# 2_0.net
KiCad netlist of a schematic drawn in Altium Designer
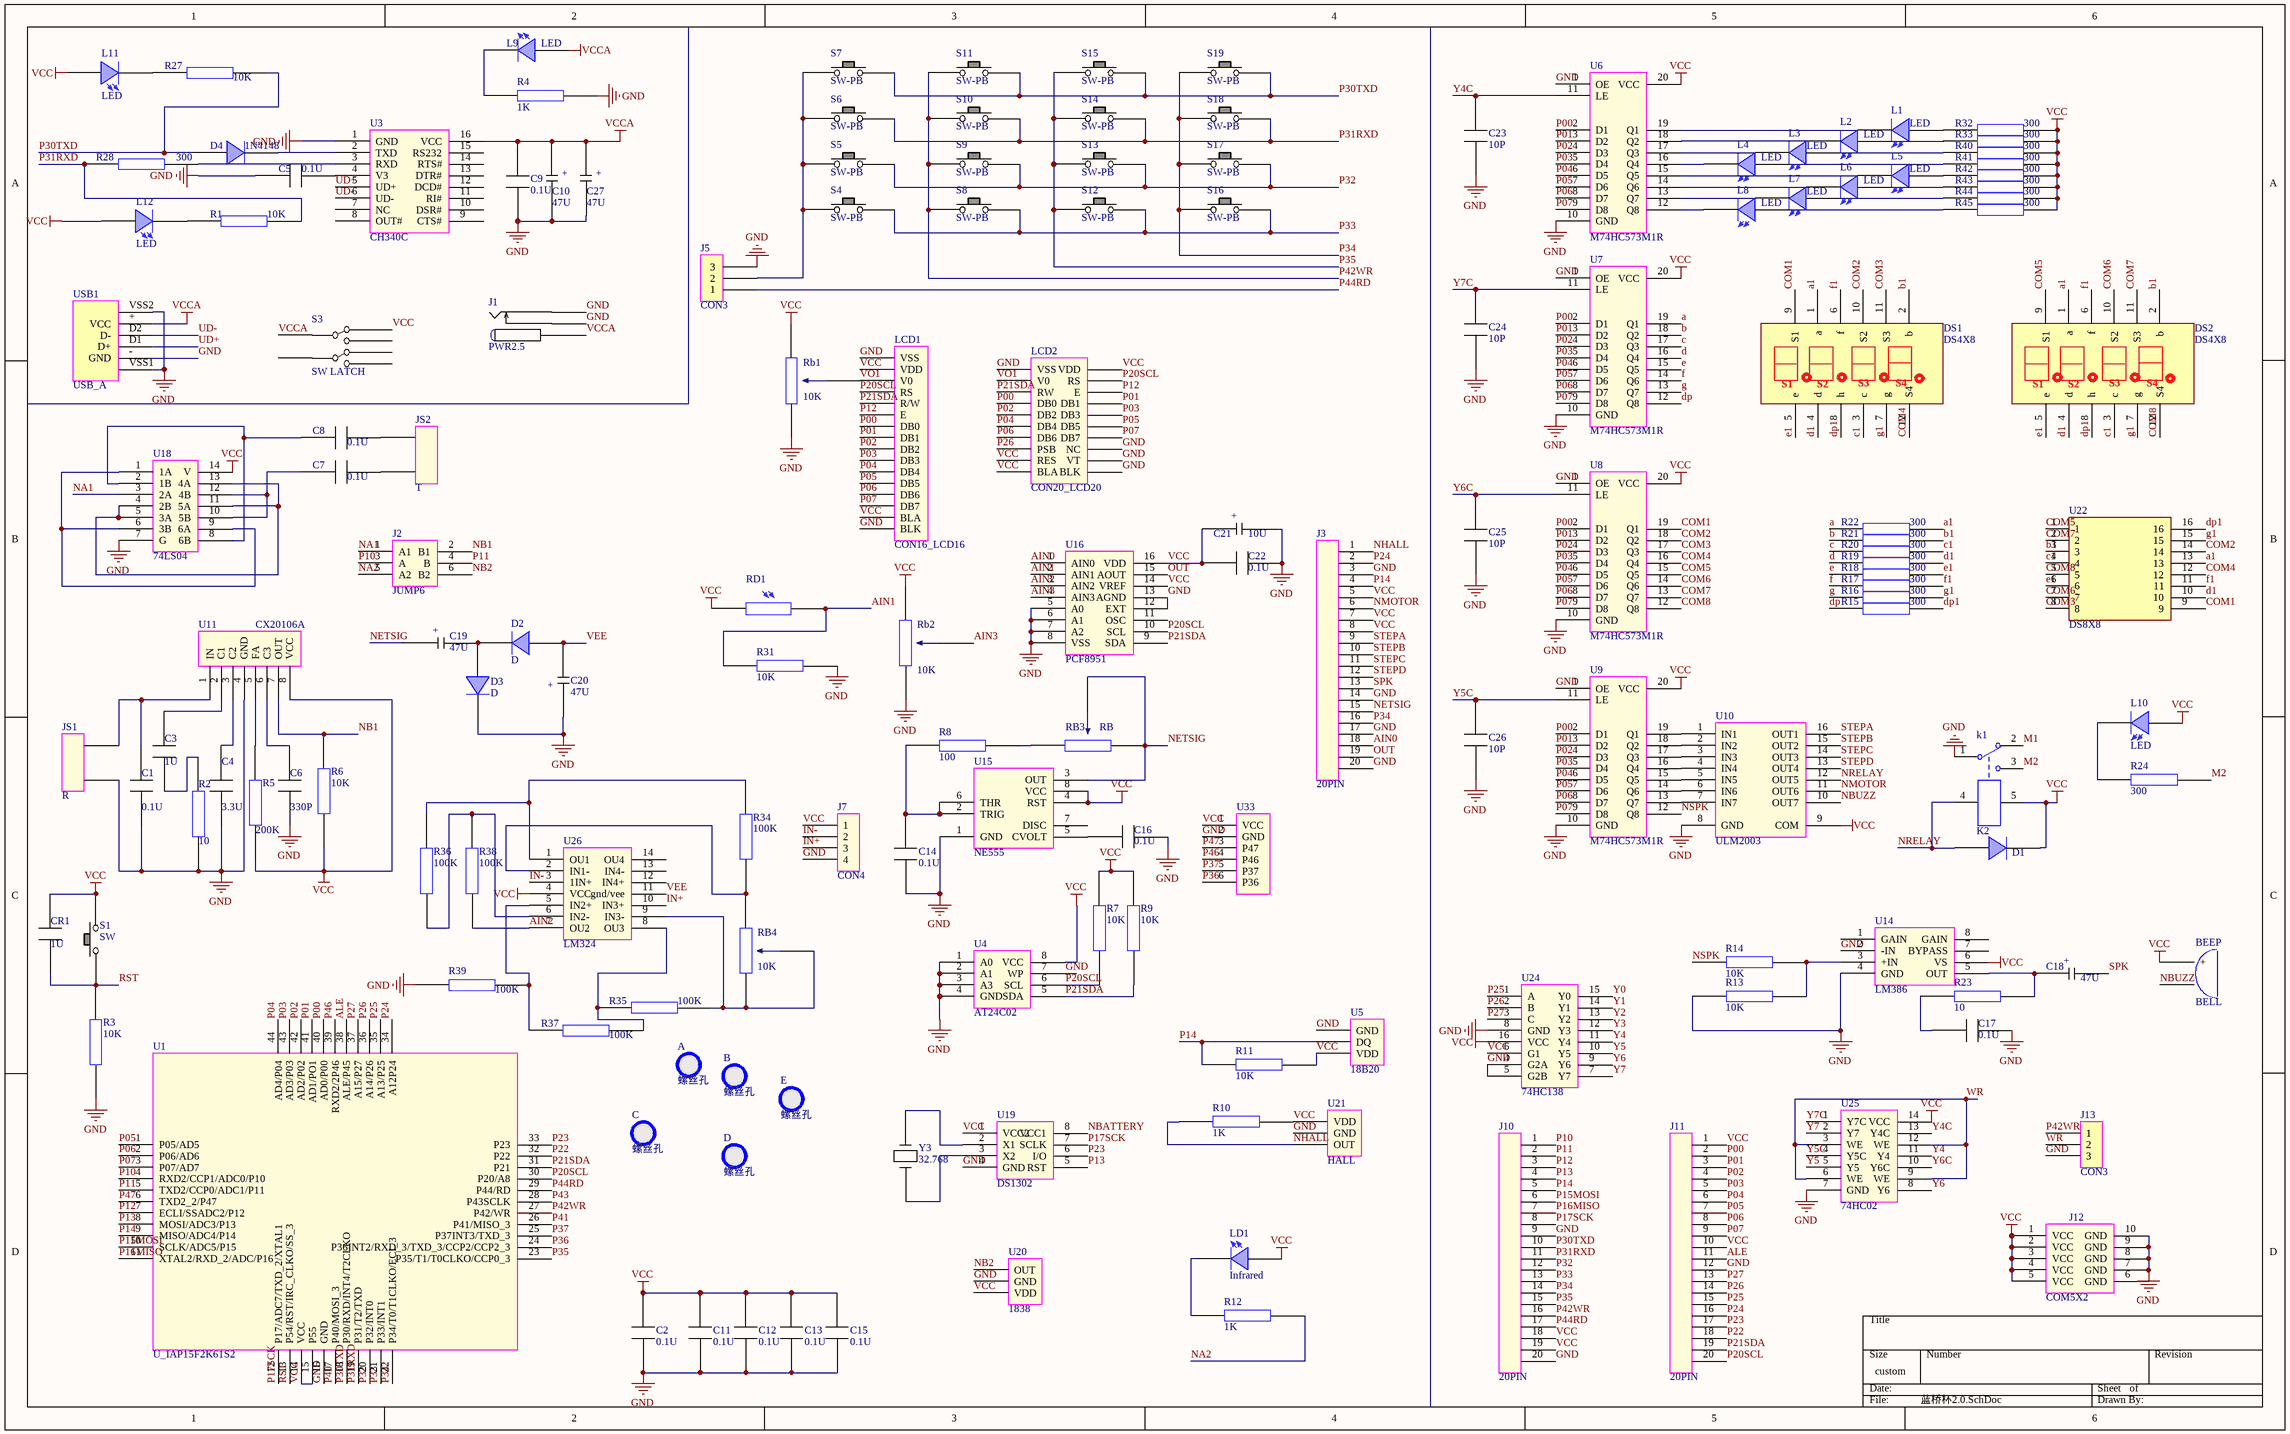
[diagram p0: 蓝桥杯2.0.SchDoc]

(export (version "E")
  (design (tool "Eeschema 10.0.6"))
  (components
    (comp (ref "A") (value "螺丝孔") (footprint "LUOSIKONG") (libsource (lib "蓝桥杯2.0板") (part "螺丝孔")))
    (comp (ref "B") (value "螺丝孔") (footprint "LUOSIKONG") (libsource (lib "蓝桥杯2.0板") (part "螺丝孔")))
    (comp (ref "BEEP") (value "BELL") (footprint "BUZZER") (libsource (lib "蓝桥杯2.0板") (part "BELL")))
    (comp (ref "C") (value "螺丝孔") (footprint "LUOSIKONG") (libsource (lib "蓝桥杯2.0板") (part "螺丝孔")))
    (comp (ref "C1") (value "0.1U") (footprint "C0805") (libsource (lib "蓝桥杯2.0板") (part "C")))
    (comp (ref "C2") (value "0.1U") (footprint "C0805") (libsource (lib "蓝桥杯2.0板") (part "C")))
    (comp (ref "C3") (value "1U") (footprint "C0805") (libsource (lib "蓝桥杯2.0板") (part "C")))
    (comp (ref "C4") (value "3.3U") (footprint "C0805") (libsource (lib "蓝桥杯2.0板") (part "C")))
    (comp (ref "C5") (value "0.1U") (footprint "C0805") (libsource (lib "蓝桥杯2.0板") (part "C")))
    (comp (ref "C6") (value "330P") (footprint "C0805") (libsource (lib "蓝桥杯2.0板") (part "C")))
    (comp (ref "C7") (value "0.1U") (footprint "C0805") (libsource (lib "蓝桥杯2.0板") (part "C")))
    (comp (ref "C8") (value "0.1U") (footprint "C0805") (libsource (lib "蓝桥杯2.0板") (part "C")))
    (comp (ref "C9") (value "0.1U") (footprint "C0805") (libsource (lib "蓝桥杯2.0板") (part "C")))
    (comp (ref "C10") (value "47U") (footprint "RVT 16V") (libsource (lib "蓝桥杯2.0板") (part "贴片电解电容")))
    (comp (ref "C11") (value "0.1U") (footprint "C0805") (libsource (lib "蓝桥杯2.0板") (part "C")))
    (comp (ref "C12") (value "0.1U") (footprint "C0805") (libsource (lib "蓝桥杯2.0板") (part "C")))
    (comp (ref "C13") (value "0.1U") (footprint "C0805") (libsource (lib "蓝桥杯2.0板") (part "C")))
    (comp (ref "C14") (value "0.1U") (footprint "C0805") (libsource (lib "蓝桥杯2.0板") (part "C")))
    (comp (ref "C15") (value "0.1U") (footprint "C0805") (libsource (lib "蓝桥杯2.0板") (part "C")))
    (comp (ref "C16") (value "0.1U") (footprint "C0805") (libsource (lib "蓝桥杯2.0板") (part "C")))
    (comp (ref "C17") (value "0.1U") (footprint "C0805") (libsource (lib "蓝桥杯2.0板") (part "C")))
    (comp (ref "C18") (value "47U") (footprint "RVT 16V") (libsource (lib "蓝桥杯2.0板") (part "贴片电解电容")))
    (comp (ref "C19") (value "47U") (footprint "RVT 16V") (libsource (lib "蓝桥杯2.0板") (part "贴片电解电容")))
    (comp (ref "C20") (value "47U") (footprint "RVT 16V") (libsource (lib "蓝桥杯2.0板") (part "贴片电解电容")))
    (comp (ref "C21") (value "10U") (footprint "RVT 16V") (libsource (lib "蓝桥杯2.0板") (part "贴片电解电容")))
    (comp (ref "C22") (value "0.1U") (footprint "C0805") (libsource (lib "蓝桥杯2.0板") (part "C")))
    (comp (ref "C23") (value "10P") (footprint "C0805") (libsource (lib "蓝桥杯2.0板") (part "C")))
    (comp (ref "C24") (value "10P") (footprint "C0805") (libsource (lib "蓝桥杯2.0板") (part "C")))
    (comp (ref "C25") (value "10P") (footprint "C0805") (libsource (lib "蓝桥杯2.0板") (part "C")))
    (comp (ref "C26") (value "10P") (footprint "C0805") (libsource (lib "蓝桥杯2.0板") (part "C")))
    (comp (ref "C27") (value "47U") (footprint "RVT 16V") (libsource (lib "蓝桥杯2.0板") (part "贴片电解电容")))
    (comp (ref "CR1") (value "1U") (footprint "C0805") (libsource (lib "蓝桥杯2.0板") (part "C")))
    (comp (ref "D") (value "螺丝孔") (footprint "LUOSIKONG") (libsource (lib "蓝桥杯2.0板") (part "螺丝孔")))
    (comp (ref "D1") (value "D") (footprint "D-DIODE-0805") (libsource (lib "蓝桥杯2.0板") (part "D")))
    (comp (ref "D2") (value "D") (footprint "D-DIODE-0805") (libsource (lib "蓝桥杯2.0板") (part "D")))
    (comp (ref "D3") (value "D") (footprint "D-DIODE-0805") (libsource (lib "蓝桥杯2.0板") (part "D")))
    (comp (ref "D4") (value "1N4148") (footprint "D-DIODE-0805") (libsource (lib "蓝桥杯2.0板") (part "D")))
    (comp (ref "DS1") (value "DS4X8") (footprint "DPY-4X8") (libsource (lib "蓝桥杯2.0板") (part "DS4X8")))
    (comp (ref "DS2") (value "DS4X8") (footprint "DPY-4X8") (libsource (lib "蓝桥杯2.0板") (part "DS4X8")))
    (comp (ref "E") (value "螺丝孔") (footprint "LUOSIKONG") (libsource (lib "蓝桥杯2.0板") (part "螺丝孔")))
    (comp (ref "J1") (value "PWR2.5") (footprint "PW 2.5") (libsource (lib "蓝桥杯2.0板") (part "PWR2.5")))
    (comp (ref "J2") (value "JUMP6") (footprint "SIP-3X2") (libsource (lib "蓝桥杯2.0板") (part "OP6")))
    (comp (ref "J3")
      (value "20PIN")
      (footprint "SIP-20 - duplicate")
      (libsource (lib "蓝桥杯2.0板") (part "P20"))
    )
    (comp (ref "J5") (value "CON3") (footprint "SIP-3") (libsource (lib "") (part "COM3_1")))
    (comp (ref "J7") (value "CON4") (footprint "SIP-4") (libsource (lib "蓝桥杯2.0板") (part "COM4")))
    (comp (ref "J10")
      (value "20PIN")
      (footprint "SIP-20 - duplicate")
      (libsource (lib "蓝桥杯2.0板") (part "P20"))
    )
    (comp (ref "J11")
      (value "20PIN")
      (footprint "SIP-20 - duplicate")
      (libsource (lib "蓝桥杯2.0板") (part "P20"))
    )
    (comp (ref "J12") (value "COM5X2") (footprint "SIP-5X2") (libsource (lib "蓝桥杯2.0板") (part "COM5X2")))
    (comp (ref "J13") (value "CON3") (footprint "SIP-3") (libsource (lib "蓝桥杯2.0板") (part "COM3")))
    (comp (ref "JS1") (value "R") (footprint "RT-16") (libsource (lib "蓝桥杯2.0板") (part "JS")))
    (comp (ref "JS2") (value "T") (footprint "RT-16") (libsource (lib "") (part "JS_1")))
    (comp (ref "k1") (value "K2") (footprint "HK-4100-F") (libsource (lib "蓝桥杯2.0板") (part "K2")))
    (comp (ref "L1") (value "LED") (footprint "L0805") (libsource (lib "蓝桥杯2.0板") (part "LED")))
    (comp (ref "L2") (value "LED") (footprint "L0805") (libsource (lib "蓝桥杯2.0板") (part "LED")))
    (comp (ref "L3") (value "LED") (footprint "L0805") (libsource (lib "蓝桥杯2.0板") (part "LED")))
    (comp (ref "L4") (value "LED") (footprint "L0805") (libsource (lib "蓝桥杯2.0板") (part "LED")))
    (comp (ref "L5") (value "LED") (footprint "L0805") (libsource (lib "蓝桥杯2.0板") (part "LED")))
    (comp (ref "L6") (value "LED") (footprint "L0805") (libsource (lib "蓝桥杯2.0板") (part "LED")))
    (comp (ref "L7") (value "LED") (footprint "L0805") (libsource (lib "蓝桥杯2.0板") (part "LED")))
    (comp (ref "L8") (value "LED") (footprint "L0805") (libsource (lib "蓝桥杯2.0板") (part "LED")))
    (comp (ref "L9") (value "LED") (footprint "L0805") (libsource (lib "蓝桥杯2.0板") (part "LED")))
    (comp (ref "L10") (value "LED") (footprint "L0805") (libsource (lib "蓝桥杯2.0板") (part "LED")))
    (comp (ref "L11") (value "LED") (footprint "L0805") (libsource (lib "蓝桥杯2.0板") (part "LED")))
    (comp (ref "L12") (value "LED") (footprint "L0805") (libsource (lib "蓝桥杯2.0板") (part "LED")))
    (comp (ref "LCD1") (value "CON16_LCD16") (footprint "SIP-16") (libsource (lib "蓝桥杯2.0板") (part "LCD16")))
    (comp (ref "LCD2") (value "CON20_LCD20") (footprint "SIP-20") (libsource (lib "蓝桥杯2.0板") (part "LCD20")))
    (comp (ref "LD1") (value "Infrared") (footprint "LED-LNF") (libsource (lib "蓝桥杯2.0板") (part "INF")))
    (comp (ref "R1") (value "10K") (footprint "R0805") (libsource (lib "蓝桥杯2.0板") (part "R")))
    (comp (ref "R2") (value "10") (footprint "R0805") (libsource (lib "蓝桥杯2.0板") (part "R")))
    (comp (ref "R3") (value "10K") (footprint "R0805") (libsource (lib "蓝桥杯2.0板") (part "R")))
    (comp (ref "R4") (value "1K") (footprint "R0805") (libsource (lib "蓝桥杯2.0板") (part "R")))
    (comp (ref "R5") (value "200K") (footprint "R0805") (libsource (lib "蓝桥杯2.0板") (part "R")))
    (comp (ref "R6") (value "10K") (footprint "R0805") (libsource (lib "蓝桥杯2.0板") (part "R")))
    (comp (ref "R7") (value "10K") (footprint "R0805") (libsource (lib "蓝桥杯2.0板") (part "R")))
    (comp (ref "R8") (value "100") (footprint "R0805") (libsource (lib "蓝桥杯2.0板") (part "R")))
    (comp (ref "R9") (value "10K") (footprint "R0805") (libsource (lib "蓝桥杯2.0板") (part "R")))
    (comp (ref "R10") (value "1K") (footprint "R0805") (libsource (lib "蓝桥杯2.0板") (part "R")))
    (comp (ref "R11") (value "10K") (footprint "R0805") (libsource (lib "蓝桥杯2.0板") (part "R")))
    (comp (ref "R12") (value "1K") (footprint "R0805") (libsource (lib "蓝桥杯2.0板") (part "R")))
    (comp (ref "R13") (value "10K") (footprint "R0805") (libsource (lib "蓝桥杯2.0板") (part "R")))
    (comp (ref "R14") (value "10K") (footprint "R0805") (libsource (lib "蓝桥杯2.0板") (part "R")))
    (comp (ref "R15") (value "300") (footprint "R0805") (libsource (lib "蓝桥杯2.0板") (part "R")))
    (comp (ref "R16") (value "300") (footprint "R0805") (libsource (lib "蓝桥杯2.0板") (part "R")))
    (comp (ref "R17") (value "300") (footprint "R0805") (libsource (lib "蓝桥杯2.0板") (part "R")))
    (comp (ref "R18") (value "300") (footprint "R0805") (libsource (lib "蓝桥杯2.0板") (part "R")))
    (comp (ref "R19") (value "300") (footprint "R0805") (libsource (lib "蓝桥杯2.0板") (part "R")))
    (comp (ref "R20") (value "300") (footprint "R0805") (libsource (lib "蓝桥杯2.0板") (part "R")))
    (comp (ref "R21") (value "300") (footprint "R0805") (libsource (lib "蓝桥杯2.0板") (part "R")))
    (comp (ref "R22") (value "300") (footprint "R0805") (libsource (lib "蓝桥杯2.0板") (part "R")))
    (comp (ref "R23") (value "10") (footprint "R0805") (libsource (lib "蓝桥杯2.0板") (part "R")))
    (comp (ref "R24") (value "300") (footprint "R0805") (libsource (lib "蓝桥杯2.0板") (part "R")))
    (comp (ref "R27") (value "10K") (footprint "R0805") (libsource (lib "蓝桥杯2.0板") (part "R")))
    (comp (ref "R28") (value "300") (footprint "R0805") (libsource (lib "蓝桥杯2.0板") (part "R")))
    (comp (ref "R31") (value "10K") (footprint "R0805") (libsource (lib "蓝桥杯2.0板") (part "R")))
    (comp (ref "R32") (value "300") (footprint "R0805") (libsource (lib "蓝桥杯2.0板") (part "R")))
    (comp (ref "R33") (value "300") (footprint "R0805") (libsource (lib "蓝桥杯2.0板") (part "R")))
    (comp (ref "R34") (value "100K") (footprint "R0805") (libsource (lib "蓝桥杯2.0板") (part "R")))
    (comp (ref "R35") (value "100K") (footprint "R0805") (libsource (lib "蓝桥杯2.0板") (part "R")))
    (comp (ref "R36") (value "100K") (footprint "R0805") (libsource (lib "蓝桥杯2.0板") (part "R")))
    (comp (ref "R37") (value "100K") (footprint "R0805") (libsource (lib "蓝桥杯2.0板") (part "R")))
    (comp (ref "R38") (value "100K") (footprint "R0805") (libsource (lib "蓝桥杯2.0板") (part "R")))
    (comp (ref "R39") (value "100K") (footprint "R0805") (libsource (lib "蓝桥杯2.0板") (part "R")))
    (comp (ref "R40") (value "300") (footprint "R0805") (libsource (lib "蓝桥杯2.0板") (part "R")))
    (comp (ref "R41") (value "300") (footprint "R0805") (libsource (lib "蓝桥杯2.0板") (part "R")))
    (comp (ref "R42") (value "300") (footprint "R0805") (libsource (lib "蓝桥杯2.0板") (part "R")))
    (comp (ref "R43") (value "300") (footprint "R0805") (libsource (lib "蓝桥杯2.0板") (part "R")))
    (comp (ref "R44") (value "300") (footprint "R0805") (libsource (lib "蓝桥杯2.0板") (part "R")))
    (comp (ref "R45") (value "300") (footprint "R0805") (libsource (lib "蓝桥杯2.0板") (part "R")))
    (comp (ref "Rb1") (value "10K") (footprint "VR-3 10") (libsource (lib "蓝桥杯2.0板") (part "RB")))
    (comp (ref "Rb2") (value "10K") (footprint "VR-3 10") (libsource (lib "蓝桥杯2.0板") (part "RB")))
    (comp (ref "RB3") (value "RB") (footprint "VR-3 10") (libsource (lib "蓝桥杯2.0板") (part "RB")))
    (comp (ref "RB4") (value "10K") (footprint "VR-3 10") (libsource (lib "蓝桥杯2.0板") (part "RB")))
    (comp (ref "RD1") (value "RD") (footprint "AXIAL-0.2") (libsource (lib "蓝桥杯2.0板") (part "RD")))
    (comp (ref "S1") (value "SW") (footprint "SKOE") (libsource (lib "") (part "贴片按键_1")))
    (comp (ref "S3") (value "SW LATCH") (footprint "SW-PB") (libsource (lib "蓝桥杯2.0板") (part "KG")))
    (comp (ref "S4") (value "SW-PB") (footprint "SKOE") (libsource (lib "蓝桥杯2.0板") (part "贴片按键")))
    (comp (ref "S5") (value "SW-PB") (footprint "SKOE") (libsource (lib "蓝桥杯2.0板") (part "贴片按键")))
    (comp (ref "S6") (value "SW-PB") (footprint "SKOE") (libsource (lib "蓝桥杯2.0板") (part "贴片按键")))
    (comp (ref "S7") (value "SW-PB") (footprint "SKOE") (libsource (lib "蓝桥杯2.0板") (part "贴片按键")))
    (comp (ref "S8") (value "SW-PB") (footprint "SKOE") (libsource (lib "蓝桥杯2.0板") (part "贴片按键")))
    (comp (ref "S9") (value "SW-PB") (footprint "SKOE") (libsource (lib "蓝桥杯2.0板") (part "贴片按键")))
    (comp (ref "S10") (value "SW-PB") (footprint "SKOE") (libsource (lib "蓝桥杯2.0板") (part "贴片按键")))
    (comp (ref "S11") (value "SW-PB") (footprint "SKOE") (libsource (lib "蓝桥杯2.0板") (part "贴片按键")))
    (comp (ref "S12") (value "SW-PB") (footprint "SKOE") (libsource (lib "蓝桥杯2.0板") (part "贴片按键")))
    (comp (ref "S13") (value "SW-PB") (footprint "SKOE") (libsource (lib "蓝桥杯2.0板") (part "贴片按键")))
    (comp (ref "S14") (value "SW-PB") (footprint "SKOE") (libsource (lib "蓝桥杯2.0板") (part "贴片按键")))
    (comp (ref "S15") (value "SW-PB") (footprint "SKOE") (libsource (lib "蓝桥杯2.0板") (part "贴片按键")))
    (comp (ref "S16") (value "SW-PB") (footprint "SKOE") (libsource (lib "蓝桥杯2.0板") (part "贴片按键")))
    (comp (ref "S17") (value "SW-PB") (footprint "SKOE") (libsource (lib "蓝桥杯2.0板") (part "贴片按键")))
    (comp (ref "S18") (value "SW-PB") (footprint "SKOE") (libsource (lib "蓝桥杯2.0板") (part "贴片按键")))
    (comp (ref "S19") (value "SW-PB") (footprint "SKOE") (libsource (lib "蓝桥杯2.0板") (part "贴片按键")))
    (comp (ref "U1")
      (value "U_IAP15F2K61S2")
      (footprint "LQFP44 - duplicate")
      (libsource (lib "转接板元件库") (part "STC15"))
    )
    (comp (ref "U3") (value "CH340C") (footprint "SOP-16") (libsource (lib "蓝桥杯2.0板") (part "CH340C")))
    (comp (ref "U4") (value "AT24C02") (footprint "SOP-8") (libsource (lib "蓝桥杯2.0板") (part "AT24C02")))
    (comp (ref "U5") (value "18B20") (footprint "TO-92") (libsource (lib "蓝桥杯2.0板") (part "18B20")))
    (comp (ref "U6")
      (value "M74HC573M1R")
      (footprint "TSOP-20(宽体)")
      (libsource (lib "蓝桥杯2.0板") (part "CH573"))
    )
    (comp (ref "U7")
      (value "M74HC573M1R")
      (footprint "TSOP-20(宽体)")
      (libsource (lib "蓝桥杯2.0板") (part "CH573"))
    )
    (comp (ref "U8")
      (value "M74HC573M1R")
      (footprint "TSOP-20(宽体)")
      (libsource (lib "蓝桥杯2.0板") (part "CH573"))
    )
    (comp (ref "U9")
      (value "M74HC573M1R")
      (footprint "TSOP-20(宽体)")
      (libsource (lib "蓝桥杯2.0板") (part "CH573"))
    )
    (comp (ref "U10") (value "ULM2003") (footprint "SOP-16") (libsource (lib "蓝桥杯2.0板") (part "ULM2003")))
    (comp (ref "U11") (value "CX20106A") (footprint "DIP-8") (libsource (lib "蓝桥杯2.0板") (part "CX20106A")))
    (comp (ref "U14") (value "LM386") (footprint "SOP-8") (libsource (lib "蓝桥杯2.0板") (part "LM386")))
    (comp (ref "U15") (value "NE555") (footprint "SOP-8") (libsource (lib "蓝桥杯2.0板") (part "NE555")))
    (comp (ref "U16")
      (value "PCF8951")
      (footprint "TSOP-16(宽体)")
      (libsource (lib "蓝桥杯2.0板") (part "PCF8951"))
    )
    (comp (ref "U18") (value "74LS04") (footprint "SOP-14") (libsource (lib "蓝桥杯2.0板") (part "74LS04")))
    (comp (ref "U19") (value "DS1302") (footprint "SOP-8") (libsource (lib "蓝桥杯2.0板") (part "DS1302")))
    (comp (ref "U20") (value "1838") (footprint "TO-92-A") (libsource (lib "蓝桥杯2.0板") (part "1838")))
    (comp (ref "U21") (value "HALL") (footprint "TO92-3") (libsource (lib "蓝桥杯2.0板") (part "HALL")))
    (comp (ref "U22") (value "DS8X8") (footprint "DPY-8X8") (libsource (lib "蓝桥杯2.0板") (part "DS8X8")))
    (comp (ref "U24") (value "74HC138") (footprint "SOP-16") (libsource (lib "蓝桥杯2.0板") (part "74HC138")))
    (comp (ref "U25") (value "74HC02") (footprint "SOP-14") (libsource (lib "蓝桥杯2.0板") (part "74HC02")))
    (comp (ref "U26") (value "LM324") (footprint "SOP-14") (libsource (lib "蓝桥杯2.0板") (part "LM324")))
    (comp (ref "U33") (value "~") (footprint "D0") (libsource (lib "蓝桥杯2.0板") (part "洞洞板")))
    (comp (ref "USB1") (value "USB_A") (footprint "USB-B") (libsource (lib "蓝桥杯2.0板") (part "USB_A")))
    (comp (ref "Y3") (value "32.768") (footprint "XTAL1-37K") (libsource (lib "蓝桥杯2.0板") (part "Y3")))
  )
  (nets
    (net (code "1") (name "/AIN0") (class "Default")
      (node (ref "J3") (pin "18") (pinfunction "18_18") (pintype "passive"))
      (node (ref "U16") (pin "1") (pinfunction "AIN0_1") (pintype "passive"))
    )
    (net (code "2") (name "/AIN1") (class "Default")
      (node (ref "R31") (pin "2") (pinfunction "2_2") (pintype "passive"))
      (node (ref "RD1") (pin "2") (pinfunction "2_2") (pintype "passive"))
      (node (ref "U16") (pin "2") (pinfunction "AIN1_2") (pintype "passive"))
    )
    (net (code "3") (name "/AIN2") (class "Default")
      (node (ref "R38") (pin "2") (pinfunction "2_2") (pintype "passive"))
      (node (ref "U16") (pin "3") (pinfunction "AIN2_3") (pintype "passive"))
      (node (ref "U26") (pin "7") (pinfunction "OU2_7") (pintype "passive"))
    )
    (net (code "4") (name "/AIN3") (class "Default")
      (node (ref "Rb2") (pin "2") (pinfunction "2_2") (pintype "passive"))
      (node (ref "U16") (pin "4") (pinfunction "AIN3_4") (pintype "passive"))
    )
    (net (code "5") (name "/ALE") (class "Default")
      (node (ref "J11") (pin "11") (pinfunction "11_11") (pintype "passive"))
      (node (ref "U1") (pin "38") (pinfunction "ALE/P45_38") (pintype "passive"))
    )
    (net (code "6") (name "/COM1") (class "Default")
      (node (ref "DS1") (pin "9") (pinfunction "S1_9") (pintype "passive"))
      (node (ref "U22") (pin "9") (pinfunction "9_9") (pintype "passive"))
      (node (ref "U8") (pin "19") (pinfunction "Q1_19") (pintype "passive"))
    )
    (net (code "7") (name "/COM2") (class "Default")
      (node (ref "DS1") (pin "10") (pinfunction "S2_10") (pintype "passive"))
      (node (ref "U22") (pin "14") (pinfunction "14_14") (pintype "passive"))
      (node (ref "U8") (pin "18") (pinfunction "Q2_18") (pintype "passive"))
    )
    (net (code "8") (name "/COM3") (class "Default")
      (node (ref "DS1") (pin "11") (pinfunction "S3_11") (pintype "passive"))
      (node (ref "U22") (pin "8") (pinfunction "8_8") (pintype "passive"))
      (node (ref "U8") (pin "17") (pinfunction "Q3_17") (pintype "passive"))
    )
    (net (code "9") (name "/COM4") (class "Default")
      (node (ref "DS1") (pin "12") (pinfunction "S4_12") (pintype "passive"))
      (node (ref "U22") (pin "12") (pinfunction "12_12") (pintype "passive"))
      (node (ref "U8") (pin "16") (pinfunction "Q4_16") (pintype "passive"))
    )
    (net (code "10") (name "/COM5") (class "Default")
      (node (ref "DS2") (pin "9") (pinfunction "S1_9") (pintype "passive"))
      (node (ref "U22") (pin "1") (pinfunction "1_1") (pintype "passive"))
      (node (ref "U8") (pin "15") (pinfunction "Q5_15") (pintype "passive"))
    )
    (net (code "11") (name "/COM6") (class "Default")
      (node (ref "DS2") (pin "10") (pinfunction "S2_10") (pintype "passive"))
      (node (ref "U22") (pin "7") (pinfunction "7_7") (pintype "passive"))
      (node (ref "U8") (pin "14") (pinfunction "Q6_14") (pintype "passive"))
    )
    (net (code "12") (name "/COM7") (class "Default")
      (node (ref "DS2") (pin "11") (pinfunction "S3_11") (pintype "passive"))
      (node (ref "U22") (pin "2") (pinfunction "2_2") (pintype "passive"))
      (node (ref "U8") (pin "13") (pinfunction "Q7_13") (pintype "passive"))
    )
    (net (code "13") (name "/COM8") (class "Default")
      (node (ref "DS2") (pin "12") (pinfunction "S4_12") (pintype "passive"))
      (node (ref "U22") (pin "5") (pinfunction "5_5") (pintype "passive"))
      (node (ref "U8") (pin "12") (pinfunction "Q8_12") (pintype "passive"))
    )
    (net (code "14") (name "/IN+") (class "Default")
      (node (ref "J7") (pin "3") (pinfunction "3_3") (pintype "passive"))
      (node (ref "U26") (pin "10") (pinfunction "IN3+_10") (pintype "passive"))
    )
    (net (code "15") (name "/IN-") (class "Default")
      (node (ref "J7") (pin "2") (pinfunction "2_2") (pintype "passive"))
      (node (ref "U26") (pin "3") (pinfunction "1IN+_3") (pintype "passive"))
    )
    (net (code "16") (name "/M1") (class "Default")
      (node (ref "k1") (pin "2") (pinfunction "2_2") (pintype "passive"))
    )
    (net (code "17") (name "/M2") (class "Default")
      (node (ref "R24") (pin "1") (pinfunction "1_1") (pintype "passive"))
      (node (ref "k1") (pin "3") (pinfunction "3_3") (pintype "passive"))
    )
    (net (code "18") (name "/NA1") (class "Default")
      (node (ref "J2") (pin "1") (pinfunction "A1_1") (pintype "passive"))
      (node (ref "U18") (pin "3") (pinfunction "2A_3") (pintype "passive"))
    )
    (net (code "19") (name "/NA2") (class "Default")
      (node (ref "J2") (pin "5") (pinfunction "A2_5") (pintype "passive"))
      (node (ref "R12") (pin "1") (pinfunction "1_1") (pintype "passive"))
    )
    (net (code "20") (name "/NB1") (class "Default")
      (node (ref "J2") (pin "2") (pinfunction "B1_2") (pintype "passive"))
      (node (ref "R6") (pin "2") (pinfunction "2_2") (pintype "passive"))
      (node (ref "U11") (pin "7") (pinfunction "OUT_7") (pintype "passive"))
    )
    (net (code "21") (name "/NB2") (class "Default")
      (node (ref "J2") (pin "6") (pinfunction "B2_6") (pintype "passive"))
      (node (ref "U20") (pin "1") (pinfunction "OUT_1") (pintype "passive"))
    )
    (net (code "22") (name "/NBATTERY") (class "Default")
      (node (ref "U19") (pin "8") (pinfunction "VCC1_8") (pintype "passive"))
    )
    (net (code "23") (name "/NBUZZ") (class "Default")
      (node (ref "BEEP") (pin "2") (pinfunction "2_2") (pintype "passive"))
      (node (ref "U10") (pin "10") (pinfunction "OUT7_10") (pintype "passive"))
    )
    (net (code "24") (name "/NETSIG") (class "Default")
      (node (ref "C19") (pin "1") (pinfunction "+_1") (pintype "passive"))
      (node (ref "J3") (pin "15") (pinfunction "15_15") (pintype "passive"))
      (node (ref "RB3") (pin "2") (pinfunction "2_2") (pintype "passive"))
      (node (ref "RB3") (pin "3") (pinfunction "3_3") (pintype "passive"))
      (node (ref "U15") (pin "3") (pinfunction "OUT_3") (pintype "passive"))
    )
    (net (code "25") (name "/NHALL") (class "Default")
      (node (ref "J3") (pin "1") (pinfunction "1_1") (pintype "passive"))
      (node (ref "R10") (pin "2") (pinfunction "2_2") (pintype "passive"))
      (node (ref "U21") (pin "3") (pinfunction "OUT_3") (pintype "passive"))
    )
    (net (code "26") (name "/NMOTOR") (class "Default")
      (node (ref "J3") (pin "6") (pinfunction "6_6") (pintype "passive"))
      (node (ref "U10") (pin "11") (pinfunction "OUT6_11") (pintype "passive"))
    )
    (net (code "27") (name "/NRELAY") (class "Default")
      (node (ref "D1") (pin "1") (pinfunction "1_1") (pintype "passive"))
      (node (ref "U10") (pin "12") (pinfunction "OUT5_12") (pintype "passive"))
      (node (ref "k1") (pin "4") (pinfunction "4_4") (pintype "passive"))
    )
    (net (code "28") (name "/NSPK") (class "Default")
      (node (ref "R14") (pin "2") (pinfunction "2_2") (pintype "passive"))
      (node (ref "U9") (pin "12") (pinfunction "Q8_12") (pintype "passive"))
    )
    (net (code "29") (name "/OUT") (class "Default")
      (node (ref "J3") (pin "19") (pinfunction "19_19") (pintype "passive"))
      (node (ref "U16") (pin "15") (pinfunction "AOUT_15") (pintype "passive"))
    )
    (net (code "30") (name "/P00") (class "Default")
      (node (ref "J11") (pin "2") (pinfunction "2_2") (pintype "passive"))
      (node (ref "LCD1") (pin "7") (pinfunction "DB0_7") (pintype "passive"))
      (node (ref "LCD2") (pin "7") (pinfunction "DB0_7") (pintype "passive"))
      (node (ref "U1") (pin "40") (pinfunction "AD0/P00_40") (pintype "passive"))
      (node (ref "U6") (pin "2") (pinfunction "D1_2") (pintype "passive"))
      (node (ref "U7") (pin "2") (pinfunction "D1_2") (pintype "passive"))
      (node (ref "U8") (pin "2") (pinfunction "D1_2") (pintype "passive"))
      (node (ref "U9") (pin "2") (pinfunction "D1_2") (pintype "passive"))
    )
    (net (code "31") (name "/P01") (class "Default")
      (node (ref "J11") (pin "3") (pinfunction "3_3") (pintype "passive"))
      (node (ref "LCD1") (pin "8") (pinfunction "DB1_8") (pintype "passive"))
      (node (ref "LCD2") (pin "8") (pinfunction "DB1_8") (pintype "passive"))
      (node (ref "U1") (pin "41") (pinfunction "AD1/PO1_41") (pintype "passive"))
      (node (ref "U6") (pin "3") (pinfunction "D2_3") (pintype "passive"))
      (node (ref "U7") (pin "3") (pinfunction "D2_3") (pintype "passive"))
      (node (ref "U8") (pin "3") (pinfunction "D2_3") (pintype "passive"))
      (node (ref "U9") (pin "3") (pinfunction "D2_3") (pintype "passive"))
    )
    (net (code "32") (name "/P02") (class "Default")
      (node (ref "J11") (pin "4") (pinfunction "4_4") (pintype "passive"))
      (node (ref "LCD1") (pin "9") (pinfunction "DB2_9") (pintype "passive"))
      (node (ref "LCD2") (pin "9") (pinfunction "DB2_9") (pintype "passive"))
      (node (ref "U1") (pin "42") (pinfunction "AD2/P02_42") (pintype "passive"))
      (node (ref "U6") (pin "4") (pinfunction "D3_4") (pintype "passive"))
      (node (ref "U7") (pin "4") (pinfunction "D3_4") (pintype "passive"))
      (node (ref "U8") (pin "4") (pinfunction "D3_4") (pintype "passive"))
      (node (ref "U9") (pin "4") (pinfunction "D3_4") (pintype "passive"))
    )
    (net (code "33") (name "/P03") (class "Default")
      (node (ref "J11") (pin "5") (pinfunction "5_5") (pintype "passive"))
      (node (ref "LCD1") (pin "10") (pinfunction "DB3_10") (pintype "passive"))
      (node (ref "LCD2") (pin "10") (pinfunction "DB3_10") (pintype "passive"))
      (node (ref "U1") (pin "43") (pinfunction "AD3/P03_43") (pintype "passive"))
      (node (ref "U6") (pin "5") (pinfunction "D4_5") (pintype "passive"))
      (node (ref "U7") (pin "5") (pinfunction "D4_5") (pintype "passive"))
      (node (ref "U8") (pin "5") (pinfunction "D4_5") (pintype "passive"))
      (node (ref "U9") (pin "5") (pinfunction "D4_5") (pintype "passive"))
    )
    (net (code "34") (name "/P04") (class "Default")
      (node (ref "J11") (pin "6") (pinfunction "6_6") (pintype "passive"))
      (node (ref "LCD1") (pin "11") (pinfunction "DB4_11") (pintype "passive"))
      (node (ref "LCD2") (pin "11") (pinfunction "DB4_11") (pintype "passive"))
      (node (ref "U1") (pin "44") (pinfunction "AD4/P04_44") (pintype "passive"))
      (node (ref "U6") (pin "6") (pinfunction "D5_6") (pintype "passive"))
      (node (ref "U7") (pin "6") (pinfunction "D5_6") (pintype "passive"))
      (node (ref "U8") (pin "6") (pinfunction "D5_6") (pintype "passive"))
      (node (ref "U9") (pin "6") (pinfunction "D5_6") (pintype "passive"))
    )
    (net (code "35") (name "/P05") (class "Default")
      (node (ref "J11") (pin "7") (pinfunction "7_7") (pintype "passive"))
      (node (ref "LCD1") (pin "12") (pinfunction "DB5_12") (pintype "passive"))
      (node (ref "LCD2") (pin "12") (pinfunction "DB5_12") (pintype "passive"))
      (node (ref "U1") (pin "1") (pinfunction "P05/AD5_1") (pintype "passive"))
      (node (ref "U6") (pin "7") (pinfunction "D6_7") (pintype "passive"))
      (node (ref "U7") (pin "7") (pinfunction "D6_7") (pintype "passive"))
      (node (ref "U8") (pin "7") (pinfunction "D6_7") (pintype "passive"))
      (node (ref "U9") (pin "7") (pinfunction "D6_7") (pintype "passive"))
    )
    (net (code "36") (name "/P06") (class "Default")
      (node (ref "J11") (pin "8") (pinfunction "8_8") (pintype "passive"))
      (node (ref "LCD1") (pin "13") (pinfunction "DB6_13") (pintype "passive"))
      (node (ref "LCD2") (pin "13") (pinfunction "DB6_13") (pintype "passive"))
      (node (ref "U1") (pin "2") (pinfunction "P06/AD6_2") (pintype "passive"))
      (node (ref "U6") (pin "8") (pinfunction "D7_8") (pintype "passive"))
      (node (ref "U7") (pin "8") (pinfunction "D7_8") (pintype "passive"))
      (node (ref "U8") (pin "8") (pinfunction "D7_8") (pintype "passive"))
      (node (ref "U9") (pin "8") (pinfunction "D7_8") (pintype "passive"))
    )
    (net (code "37") (name "/P07") (class "Default")
      (node (ref "J11") (pin "9") (pinfunction "9_9") (pintype "passive"))
      (node (ref "LCD1") (pin "14") (pinfunction "DB7_14") (pintype "passive"))
      (node (ref "LCD2") (pin "14") (pinfunction "DB7_14") (pintype "passive"))
      (node (ref "U1") (pin "3") (pinfunction "P07/AD7_3") (pintype "passive"))
      (node (ref "U6") (pin "9") (pinfunction "D8_9") (pintype "passive"))
      (node (ref "U7") (pin "9") (pinfunction "D8_9") (pintype "passive"))
      (node (ref "U8") (pin "9") (pinfunction "D8_9") (pintype "passive"))
      (node (ref "U9") (pin "9") (pinfunction "D8_9") (pintype "passive"))
    )
    (net (code "38") (name "/P10") (class "Default")
      (node (ref "J10") (pin "1") (pinfunction "1_1") (pintype "passive"))
      (node (ref "J2") (pin "3") (pinfunction "A_3") (pintype "passive"))
      (node (ref "U1") (pin "4") (pinfunction "RXD2/CCP1/ADC0/P10_4") (pintype "passive"))
    )
    (net (code "39") (name "/P11") (class "Default")
      (node (ref "J10") (pin "2") (pinfunction "2_2") (pintype "passive"))
      (node (ref "J2") (pin "4") (pinfunction "B_4") (pintype "passive"))
      (node (ref "U1") (pin "5") (pinfunction "TXD2/CCP0/ADC1/P11_5") (pintype "passive"))
    )
    (net (code "40") (name "/P12") (class "Default")
      (node (ref "J10") (pin "3") (pinfunction "3_3") (pintype "passive"))
      (node (ref "LCD1") (pin "6") (pinfunction "E_6") (pintype "passive"))
      (node (ref "LCD2") (pin "6") (pinfunction "E_6") (pintype "passive"))
      (node (ref "U1") (pin "7") (pinfunction "ECLI/SSADC2/P12_7") (pintype "passive"))
    )
    (net (code "41") (name "/P13") (class "Default")
      (node (ref "J10") (pin "4") (pinfunction "4_4") (pintype "passive"))
      (node (ref "U1") (pin "8") (pinfunction "MOSI/ADC3/P13_8") (pintype "passive"))
      (node (ref "U19") (pin "5") (pinfunction "RST_5") (pintype "passive"))
    )
    (net (code "42") (name "/P14") (class "Default")
      (node (ref "J10") (pin "5") (pinfunction "5_5") (pintype "passive"))
      (node (ref "J3") (pin "4") (pinfunction "4_4") (pintype "passive"))
      (node (ref "R11") (pin "2") (pinfunction "2_2") (pintype "passive"))
      (node (ref "U1") (pin "9") (pinfunction "MISO/ADC4/P14_9") (pintype "passive"))
      (node (ref "U5") (pin "2") (pinfunction "DQ_2") (pintype "passive"))
    )
    (net (code "43") (name "/P15MOSI") (class "Default")
      (node (ref "J10") (pin "6") (pinfunction "6_6") (pintype "passive"))
      (node (ref "U1") (pin "10") (pinfunction "SCLK/ADC5/P15_10") (pintype "passive"))
    )
    (net (code "44") (name "/P16MISO") (class "Default")
      (node (ref "J10") (pin "7") (pinfunction "7_7") (pintype "passive"))
      (node (ref "U1") (pin "11") (pinfunction "XTAL2/RXD_2/ADC/P16_11") (pintype "passive"))
    )
    (net (code "45") (name "/P17SCK") (class "Default")
      (node (ref "J10") (pin "8") (pinfunction "8_8") (pintype "passive"))
      (node (ref "U1") (pin "12") (pinfunction "P17/ADC7/TXD_2/XTAL1_12") (pintype "passive"))
      (node (ref "U19") (pin "7") (pinfunction "SCLK_7") (pintype "passive"))
    )
    (net (code "46") (name "/P20SCL") (class "Default")
      (node (ref "J11") (pin "20") (pinfunction "20_20") (pintype "passive"))
      (node (ref "LCD1") (pin "4") (pinfunction "RS_4") (pintype "passive"))
      (node (ref "LCD2") (pin "4") (pinfunction "RS_4") (pintype "passive"))
      (node (ref "R7") (pin "1") (pinfunction "1_1") (pintype "passive"))
      (node (ref "U1") (pin "30") (pinfunction "P20/A8_30") (pintype "passive"))
      (node (ref "U16") (pin "10") (pinfunction "SCL_10") (pintype "passive"))
      (node (ref "U4") (pin "6") (pinfunction "SCL_6") (pintype "passive"))
    )
    (net (code "47") (name "/P21SDA") (class "Default")
      (node (ref "J11") (pin "19") (pinfunction "19_19") (pintype "passive"))
      (node (ref "LCD1") (pin "5") (pinfunction "R/W_5") (pintype "passive"))
      (node (ref "LCD2") (pin "5") (pinfunction "RW_5") (pintype "passive"))
      (node (ref "R9") (pin "1") (pinfunction "1_1") (pintype "passive"))
      (node (ref "U1") (pin "31") (pinfunction "P21_31") (pintype "passive"))
      (node (ref "U16") (pin "9") (pinfunction "SDA_9") (pintype "passive"))
      (node (ref "U4") (pin "5") (pinfunction "SDA_5") (pintype "passive"))
    )
    (net (code "48") (name "/P22") (class "Default")
      (node (ref "J11") (pin "18") (pinfunction "18_18") (pintype "passive"))
      (node (ref "U1") (pin "32") (pinfunction "P22_32") (pintype "passive"))
    )
    (net (code "49") (name "/P23") (class "Default")
      (node (ref "J11") (pin "17") (pinfunction "17_17") (pintype "passive"))
      (node (ref "U1") (pin "33") (pinfunction "P23_33") (pintype "passive"))
      (node (ref "U19") (pin "6") (pinfunction "I/O_6") (pintype "passive"))
    )
    (net (code "50") (name "/P24") (class "Default")
      (node (ref "J11") (pin "16") (pinfunction "16_16") (pintype "passive"))
      (node (ref "J3") (pin "2") (pinfunction "2_2") (pintype "passive"))
      (node (ref "U1") (pin "34") (pinfunction "A12P24_34") (pintype "passive"))
    )
    (net (code "51") (name "/P25") (class "Default")
      (node (ref "J11") (pin "15") (pinfunction "15_15") (pintype "passive"))
      (node (ref "U1") (pin "35") (pinfunction "A13/P25_35") (pintype "passive"))
      (node (ref "U24") (pin "1") (pinfunction "A_1") (pintype "passive"))
    )
    (net (code "52") (name "/P26") (class "Default")
      (node (ref "J11") (pin "14") (pinfunction "14_14") (pintype "passive"))
      (node (ref "LCD2") (pin "15") (pinfunction "PSB_15") (pintype "passive"))
      (node (ref "U1") (pin "36") (pinfunction "A14/P26_36") (pintype "passive"))
      (node (ref "U24") (pin "2") (pinfunction "B_2") (pintype "passive"))
    )
    (net (code "53") (name "/P27") (class "Default")
      (node (ref "J11") (pin "13") (pinfunction "13_13") (pintype "passive"))
      (node (ref "U1") (pin "37") (pinfunction "A15/P27_37") (pintype "passive"))
      (node (ref "U24") (pin "3") (pinfunction "C_3") (pintype "passive"))
    )
    (net (code "54") (name "/P30TXD") (class "Default")
      (node (ref "D4") (pin "1") (pinfunction "1_1") (pintype "passive"))
      (node (ref "J10") (pin "10") (pinfunction "10_10") (pintype "passive"))
      (node (ref "R27") (pin "1") (pinfunction "1_1") (pintype "passive"))
      (node (ref "S11") (pin "1") (pinfunction "1_1") (pintype "passive"))
      (node (ref "S15") (pin "1") (pinfunction "1_1") (pintype "passive"))
      (node (ref "S19") (pin "1") (pinfunction "1_1") (pintype "passive"))
      (node (ref "S7") (pin "1") (pinfunction "1_1") (pintype "passive"))
      (node (ref "U1") (pin "18") (pinfunction "P30/RXD/INT4/T2CLKO_18") (pintype "passive"))
    )
    (net (code "55") (name "/P31RXD") (class "Default")
      (node (ref "J10") (pin "11") (pinfunction "11_11") (pintype "passive"))
      (node (ref "R1") (pin "1") (pinfunction "1_1") (pintype "passive"))
      (node (ref "R28") (pin "2") (pinfunction "2_2") (pintype "passive"))
      (node (ref "S10") (pin "1") (pinfunction "1_1") (pintype "passive"))
      (node (ref "S14") (pin "1") (pinfunction "1_1") (pintype "passive"))
      (node (ref "S18") (pin "1") (pinfunction "1_1") (pintype "passive"))
      (node (ref "S6") (pin "1") (pinfunction "1_1") (pintype "passive"))
      (node (ref "U1") (pin "19") (pinfunction "P31/T2/TXD_19") (pintype "passive"))
    )
    (net (code "56") (name "/P32") (class "Default")
      (node (ref "J10") (pin "12") (pinfunction "12_12") (pintype "passive"))
      (node (ref "S13") (pin "1") (pinfunction "1_1") (pintype "passive"))
      (node (ref "S17") (pin "1") (pinfunction "1_1") (pintype "passive"))
      (node (ref "S5") (pin "1") (pinfunction "1_1") (pintype "passive"))
      (node (ref "S9") (pin "1") (pinfunction "1_1") (pintype "passive"))
      (node (ref "U1") (pin "20") (pinfunction "P32/INT0_20") (pintype "passive"))
    )
    (net (code "57") (name "/P33") (class "Default")
      (node (ref "J10") (pin "13") (pinfunction "13_13") (pintype "passive"))
      (node (ref "S12") (pin "1") (pinfunction "1_1") (pintype "passive"))
      (node (ref "S16") (pin "1") (pinfunction "1_1") (pintype "passive"))
      (node (ref "S4") (pin "1") (pinfunction "1_1") (pintype "passive"))
      (node (ref "S8") (pin "1") (pinfunction "1_1") (pintype "passive"))
      (node (ref "U1") (pin "21") (pinfunction "P33/INT1_21") (pintype "passive"))
    )
    (net (code "58") (name "/P34") (class "Default")
      (node (ref "J10") (pin "14") (pinfunction "14_14") (pintype "passive"))
      (node (ref "J3") (pin "16") (pinfunction "16_16") (pintype "passive"))
      (node (ref "S16") (pin "2") (pinfunction "2_2") (pintype "passive"))
      (node (ref "S17") (pin "2") (pinfunction "2_2") (pintype "passive"))
      (node (ref "S18") (pin "2") (pinfunction "2_2") (pintype "passive"))
      (node (ref "S19") (pin "2") (pinfunction "2_2") (pintype "passive"))
      (node (ref "U1") (pin "22") (pinfunction "P34/T0/T1CLKO/ECI_3_22") (pintype "passive"))
    )
    (net (code "59") (name "/P35") (class "Default")
      (node (ref "J10") (pin "15") (pinfunction "15_15") (pintype "passive"))
      (node (ref "S12") (pin "2") (pinfunction "2_2") (pintype "passive"))
      (node (ref "S13") (pin "2") (pinfunction "2_2") (pintype "passive"))
      (node (ref "S14") (pin "2") (pinfunction "2_2") (pintype "passive"))
      (node (ref "S15") (pin "2") (pinfunction "2_2") (pintype "passive"))
      (node (ref "U1") (pin "23") (pinfunction "P35/T1/T0CLKO/CCP0_3_23") (pintype "passive"))
    )
    (net (code "60") (name "/P36") (class "Default")
      (node (ref "U1") (pin "24") (pinfunction "P36INT2/RXD_3/TXD_3/CCP2/CCP2_3_24") (pintype "passive"))
      (node (ref "U33") (pin "6") (pinfunction "P36_6") (pintype "passive"))
    )
    (net (code "61") (name "/P37") (class "Default")
      (node (ref "U1") (pin "25") (pinfunction "P37INT3/TXD_3_25") (pintype "passive"))
      (node (ref "U33") (pin "5") (pinfunction "P37_5") (pintype "passive"))
    )
    (net (code "62") (name "/P40") (class "Default")
      (node (ref "U1") (pin "17") (pinfunction "P40/MOSI_3_17") (pintype "passive"))
    )
    (net (code "63") (name "/P41") (class "Default")
      (node (ref "U1") (pin "26") (pinfunction "P41/MISO_3_26") (pintype "passive"))
    )
    (net (code "64") (name "/P42WR") (class "Default")
      (node (ref "J10") (pin "16") (pinfunction "16_16") (pintype "passive"))
      (node (ref "J13") (pin "1") (pinfunction "1_1") (pintype "passive"))
      (node (ref "S10") (pin "2") (pinfunction "2_2") (pintype "passive"))
      (node (ref "S11") (pin "2") (pinfunction "2_2") (pintype "passive"))
      (node (ref "S8") (pin "2") (pinfunction "2_2") (pintype "passive"))
      (node (ref "S9") (pin "2") (pinfunction "2_2") (pintype "passive"))
      (node (ref "U1") (pin "27") (pinfunction "P42/WR_27") (pintype "passive"))
    )
    (net (code "65") (name "/P43") (class "Default")
      (node (ref "U1") (pin "28") (pinfunction "P43SCLK_28") (pintype "passive"))
    )
    (net (code "66") (name "/P44RD") (class "Default")
      (node (ref "J10") (pin "17") (pinfunction "17_17") (pintype "passive"))
      (node (ref "J5") (pin "1") (pinfunction "1_1") (pintype "passive"))
      (node (ref "U1") (pin "29") (pinfunction "P44/RD_29") (pintype "passive"))
    )
    (net (code "67") (name "/P46") (class "Default")
      (node (ref "U1") (pin "39") (pinfunction "RXD2/2P46_39") (pintype "passive"))
      (node (ref "U33") (pin "4") (pinfunction "P46_4") (pintype "passive"))
    )
    (net (code "68") (name "/P47") (class "Default")
      (node (ref "U1") (pin "6") (pinfunction "TXD2_2/P47_6") (pintype "passive"))
      (node (ref "U33") (pin "3") (pinfunction "P47_3") (pintype "passive"))
    )
    (net (code "69") (name "/RST") (class "Default")
      (node (ref "CR1") (pin "1") (pinfunction "1_1") (pintype "passive"))
      (node (ref "R3") (pin "2") (pinfunction "2_2") (pintype "passive"))
      (node (ref "S1") (pin "2") (pinfunction "2_2") (pintype "passive"))
      (node (ref "U1") (pin "13") (pinfunction "P54/RST/IRC_CLKO/SS_3_13") (pintype "passive"))
    )
    (net (code "70") (name "/SPK") (class "Default")
      (node (ref "C18") (pin "2") (pinfunction "-_2") (pintype "passive"))
      (node (ref "J3") (pin "13") (pinfunction "13_13") (pintype "passive"))
    )
    (net (code "71") (name "/STEPA") (class "Default")
      (node (ref "J3") (pin "9") (pinfunction "9_9") (pintype "passive"))
      (node (ref "U10") (pin "16") (pinfunction "OUT1_16") (pintype "passive"))
    )
    (net (code "72") (name "/STEPB") (class "Default")
      (node (ref "J3") (pin "10") (pinfunction "10_10") (pintype "passive"))
      (node (ref "U10") (pin "15") (pinfunction "OUT2_15") (pintype "passive"))
    )
    (net (code "73") (name "/STEPC") (class "Default")
      (node (ref "J3") (pin "11") (pinfunction "11_11") (pintype "passive"))
      (node (ref "U10") (pin "14") (pinfunction "OUT3_14") (pintype "passive"))
    )
    (net (code "74") (name "/STEPD") (class "Default")
      (node (ref "J3") (pin "12") (pinfunction "12_12") (pintype "passive"))
      (node (ref "U10") (pin "13") (pinfunction "OUT4_13") (pintype "passive"))
    )
    (net (code "75") (name "/UD+") (class "Default")
      (node (ref "U3") (pin "5") (pinfunction "UD+_5") (pintype "passive"))
      (node (ref "USB1") (pin "D1") (pinfunction "D+_D1") (pintype "passive"))
    )
    (net (code "76") (name "/UD-") (class "Default")
      (node (ref "U3") (pin "6") (pinfunction "UD-_6") (pintype "passive"))
      (node (ref "USB1") (pin "D2") (pinfunction "D-_D2") (pintype "passive"))
    )
    (net (code "77") (name "/VEE") (class "Default")
      (node (ref "C20") (pin "2") (pinfunction "-_2") (pintype "passive"))
      (node (ref "D2") (pin "1") (pinfunction "1_1") (pintype "passive"))
      (node (ref "U26") (pin "11") (pinfunction "gnd/vee_11") (pintype "passive"))
    )
    (net (code "78") (name "/VO1") (class "Default")
      (node (ref "LCD1") (pin "3") (pinfunction "V0_3") (pintype "passive"))
      (node (ref "LCD2") (pin "3") (pinfunction "V0_3") (pintype "passive"))
      (node (ref "Rb1") (pin "2") (pinfunction "2_2") (pintype "passive"))
    )
    (net (code "79") (name "/WR") (class "Default")
      (node (ref "J13") (pin "2") (pinfunction "2_2") (pintype "passive"))
      (node (ref "U25") (pin "12") (pinfunction "WE_12") (pintype "passive"))
      (node (ref "U25") (pin "3") (pinfunction "WE_3") (pintype "passive"))
      (node (ref "U25") (pin "6") (pinfunction "WE_6") (pintype "passive"))
      (node (ref "U25") (pin "9") (pinfunction "WE_9") (pintype "passive"))
    )
    (net (code "80") (name "/Y0") (class "Default")
      (node (ref "U24") (pin "15") (pinfunction "Y0_15") (pintype "passive"))
    )
    (net (code "81") (name "/Y1") (class "Default")
      (node (ref "U24") (pin "14") (pinfunction "Y1_14") (pintype "passive"))
    )
    (net (code "82") (name "/Y2") (class "Default")
      (node (ref "U24") (pin "13") (pinfunction "Y2_13") (pintype "passive"))
    )
    (net (code "83") (name "/Y3") (class "Default")
      (node (ref "U24") (pin "12") (pinfunction "Y3_12") (pintype "passive"))
    )
    (net (code "84") (name "/Y4") (class "Default")
      (node (ref "U24") (pin "11") (pinfunction "Y4_11") (pintype "passive"))
      (node (ref "U25") (pin "11") (pinfunction "Y4_11") (pintype "passive"))
    )
    (net (code "85") (name "/Y4C") (class "Default")
      (node (ref "C23") (pin "2") (pinfunction "2_2") (pintype "passive"))
      (node (ref "U25") (pin "13") (pinfunction "Y4C_13") (pintype "passive"))
      (node (ref "U6") (pin "11") (pinfunction "LE_11") (pintype "passive"))
    )
    (net (code "86") (name "/Y5") (class "Default")
      (node (ref "U24") (pin "10") (pinfunction "Y5_10") (pintype "passive"))
      (node (ref "U25") (pin "5") (pinfunction "Y5_5") (pintype "passive"))
    )
    (net (code "87") (name "/Y5C") (class "Default")
      (node (ref "C26") (pin "2") (pinfunction "2_2") (pintype "passive"))
      (node (ref "U25") (pin "4") (pinfunction "Y5C_4") (pintype "passive"))
      (node (ref "U9") (pin "11") (pinfunction "LE_11") (pintype "passive"))
    )
    (net (code "88") (name "/Y6") (class "Default")
      (node (ref "U24") (pin "9") (pinfunction "Y6_9") (pintype "passive"))
      (node (ref "U25") (pin "8") (pinfunction "Y6_8") (pintype "passive"))
    )
    (net (code "89") (name "/Y6C") (class "Default")
      (node (ref "C25") (pin "2") (pinfunction "2_2") (pintype "passive"))
      (node (ref "U25") (pin "10") (pinfunction "Y6C_10") (pintype "passive"))
      (node (ref "U8") (pin "11") (pinfunction "LE_11") (pintype "passive"))
    )
    (net (code "90") (name "/Y7") (class "Default")
      (node (ref "U24") (pin "7") (pinfunction "Y7_7") (pintype "passive"))
      (node (ref "U25") (pin "2") (pinfunction "Y7_2") (pintype "passive"))
    )
    (net (code "91") (name "/Y7C") (class "Default")
      (node (ref "C24") (pin "2") (pinfunction "2_2") (pintype "passive"))
      (node (ref "U25") (pin "1") (pinfunction "Y7C_1") (pintype "passive"))
      (node (ref "U7") (pin "11") (pinfunction "LE_11") (pintype "passive"))
    )
    (net (code "92") (name "/a") (class "Default")
      (node (ref "R22") (pin "2") (pinfunction "2_2") (pintype "passive"))
      (node (ref "U7") (pin "19") (pinfunction "Q1_19") (pintype "passive"))
    )
    (net (code "93") (name "/a1") (class "Default")
      (node (ref "DS1") (pin "1") (pinfunction "a_1") (pintype "passive"))
      (node (ref "DS2") (pin "1") (pinfunction "a_1") (pintype "passive"))
      (node (ref "R22") (pin "1") (pinfunction "1_1") (pintype "passive"))
      (node (ref "U22") (pin "13") (pinfunction "13_13") (pintype "passive"))
    )
    (net (code "94") (name "/b") (class "Default")
      (node (ref "R21") (pin "2") (pinfunction "2_2") (pintype "passive"))
      (node (ref "U7") (pin "18") (pinfunction "Q2_18") (pintype "passive"))
    )
    (net (code "95") (name "/b1") (class "Default")
      (node (ref "DS1") (pin "2") (pinfunction "b_2") (pintype "passive"))
      (node (ref "DS2") (pin "2") (pinfunction "b_2") (pintype "passive"))
      (node (ref "R21") (pin "1") (pinfunction "1_1") (pintype "passive"))
      (node (ref "U22") (pin "3") (pinfunction "3_3") (pintype "passive"))
    )
    (net (code "96") (name "/c") (class "Default")
      (node (ref "R20") (pin "2") (pinfunction "2_2") (pintype "passive"))
      (node (ref "U7") (pin "17") (pinfunction "Q3_17") (pintype "passive"))
    )
    (net (code "97") (name "/c1") (class "Default")
      (node (ref "DS1") (pin "3") (pinfunction "c_3") (pintype "passive"))
      (node (ref "DS2") (pin "3") (pinfunction "c_3") (pintype "passive"))
      (node (ref "R20") (pin "1") (pinfunction "1_1") (pintype "passive"))
      (node (ref "U22") (pin "4") (pinfunction "4_4") (pintype "passive"))
    )
    (net (code "98") (name "/d") (class "Default")
      (node (ref "R19") (pin "2") (pinfunction "2_2") (pintype "passive"))
      (node (ref "U7") (pin "16") (pinfunction "Q4_16") (pintype "passive"))
    )
    (net (code "99") (name "/d1") (class "Default")
      (node (ref "DS1") (pin "4") (pinfunction "d_4") (pintype "passive"))
      (node (ref "DS2") (pin "4") (pinfunction "d_4") (pintype "passive"))
      (node (ref "R19") (pin "1") (pinfunction "1_1") (pintype "passive"))
      (node (ref "U22") (pin "10") (pinfunction "10_10") (pintype "passive"))
    )
    (net (code "100") (name "/dp") (class "Default")
      (node (ref "R15") (pin "2") (pinfunction "2_2") (pintype "passive"))
      (node (ref "U7") (pin "12") (pinfunction "Q8_12") (pintype "passive"))
    )
    (net (code "101") (name "/dp1") (class "Default")
      (node (ref "DS1") (pin "8") (pinfunction "h_8") (pintype "passive"))
      (node (ref "DS2") (pin "8") (pinfunction "h_8") (pintype "passive"))
      (node (ref "R15") (pin "1") (pinfunction "1_1") (pintype "passive"))
      (node (ref "U22") (pin "16") (pinfunction "16_16") (pintype "passive"))
    )
    (net (code "102") (name "/e") (class "Default")
      (node (ref "R18") (pin "2") (pinfunction "2_2") (pintype "passive"))
      (node (ref "U7") (pin "15") (pinfunction "Q5_15") (pintype "passive"))
    )
    (net (code "103") (name "/e1") (class "Default")
      (node (ref "DS1") (pin "5") (pinfunction "e_5") (pintype "passive"))
      (node (ref "DS2") (pin "5") (pinfunction "e_5") (pintype "passive"))
      (node (ref "R18") (pin "1") (pinfunction "1_1") (pintype "passive"))
      (node (ref "U22") (pin "6") (pinfunction "6_6") (pintype "passive"))
    )
    (net (code "104") (name "/f") (class "Default")
      (node (ref "R17") (pin "2") (pinfunction "2_2") (pintype "passive"))
      (node (ref "U7") (pin "14") (pinfunction "Q6_14") (pintype "passive"))
    )
    (net (code "105") (name "/f1") (class "Default")
      (node (ref "DS1") (pin "6") (pinfunction "f_6") (pintype "passive"))
      (node (ref "DS2") (pin "6") (pinfunction "f_6") (pintype "passive"))
      (node (ref "R17") (pin "1") (pinfunction "1_1") (pintype "passive"))
      (node (ref "U22") (pin "11") (pinfunction "11_11") (pintype "passive"))
    )
    (net (code "106") (name "/g") (class "Default")
      (node (ref "R16") (pin "2") (pinfunction "2_2") (pintype "passive"))
      (node (ref "U7") (pin "13") (pinfunction "Q7_13") (pintype "passive"))
    )
    (net (code "107") (name "/g1") (class "Default")
      (node (ref "DS1") (pin "7") (pinfunction "g_7") (pintype "passive"))
      (node (ref "DS2") (pin "7") (pinfunction "g_7") (pintype "passive"))
      (node (ref "R16") (pin "1") (pinfunction "1_1") (pintype "passive"))
      (node (ref "U22") (pin "15") (pinfunction "15_15") (pintype "passive"))
    )
    (net (code "108") (name "GND") (class "Default")
      (node (ref "C1") (pin "1") (pinfunction "1_1") (pintype "passive"))
      (node (ref "C10") (pin "2") (pinfunction "-_2") (pintype "passive"))
      (node (ref "C11") (pin "1") (pinfunction "1_1") (pintype "passive"))
      (node (ref "C12") (pin "1") (pinfunction "1_1") (pintype "passive"))
      (node (ref "C13") (pin "1") (pinfunction "1_1") (pintype "passive"))
      (node (ref "C14") (pin "1") (pinfunction "1_1") (pintype "passive"))
      (node (ref "C15") (pin "1") (pinfunction "1_1") (pintype "passive"))
      (node (ref "C16") (pin "2") (pinfunction "2_2") (pintype "passive"))
      (node (ref "C17") (pin "2") (pinfunction "2_2") (pintype "passive"))
      (node (ref "C2") (pin "1") (pinfunction "1_1") (pintype "passive"))
      (node (ref "C20") (pin "1") (pinfunction "+_1") (pintype "passive"))
      (node (ref "C21") (pin "2") (pinfunction "-_2") (pintype "passive"))
      (node (ref "C22") (pin "2") (pinfunction "2_2") (pintype "passive"))
      (node (ref "C23") (pin "1") (pinfunction "1_1") (pintype "passive"))
      (node (ref "C24") (pin "1") (pinfunction "1_1") (pintype "passive"))
      (node (ref "C25") (pin "1") (pinfunction "1_1") (pintype "passive"))
      (node (ref "C26") (pin "1") (pinfunction "1_1") (pintype "passive"))
      (node (ref "C27") (pin "2") (pinfunction "-_2") (pintype "passive"))
      (node (ref "C4") (pin "1") (pinfunction "1_1") (pintype "passive"))
      (node (ref "C5") (pin "1") (pinfunction "1_1") (pintype "passive"))
      (node (ref "C6") (pin "1") (pinfunction "1_1") (pintype "passive"))
      (node (ref "C9") (pin "1") (pinfunction "1_1") (pintype "passive"))
      (node (ref "D3") (pin "2") (pinfunction "2_2") (pintype "passive"))
      (node (ref "J1") (pin "GND") (pinfunction "GND_GND") (pintype "passive"))
      (node (ref "J10") (pin "20") (pinfunction "20_20") (pintype "passive"))
      (node (ref "J10") (pin "9") (pinfunction "9_9") (pintype "passive"))
      (node (ref "J11") (pin "12") (pinfunction "12_12") (pintype "passive"))
      (node (ref "J12") (pin "10") (pinfunction "GND_10") (pintype "passive"))
      (node (ref "J12") (pin "6") (pinfunction "GND_6") (pintype "passive"))
      (node (ref "J12") (pin "7") (pinfunction "GND_7") (pintype "passive"))
      (node (ref "J12") (pin "8") (pinfunction "GND_8") (pintype "passive"))
      (node (ref "J12") (pin "9") (pinfunction "GND_9") (pintype "passive"))
      (node (ref "J13") (pin "3") (pinfunction "3_3") (pintype "passive"))
      (node (ref "J3") (pin "14") (pinfunction "14_14") (pintype "passive"))
      (node (ref "J3") (pin "17") (pinfunction "17_17") (pintype "passive"))
      (node (ref "J3") (pin "20") (pinfunction "20_20") (pintype "passive"))
      (node (ref "J3") (pin "3") (pinfunction "3_3") (pintype "passive"))
      (node (ref "J5") (pin "3") (pinfunction "3_3") (pintype "passive"))
      (node (ref "J7") (pin "4") (pinfunction "4_4") (pintype "passive"))
      (node (ref "JS1") (pin "2") (pinfunction "2_2") (pintype "passive"))
      (node (ref "LCD1") (pin "1") (pinfunction "VSS_1") (pintype "passive"))
      (node (ref "LCD1") (pin "16") (pinfunction "BLK_16") (pintype "passive"))
      (node (ref "LCD2") (pin "1") (pinfunction "VSS_1") (pintype "passive"))
      (node (ref "LCD2") (pin "16") (pinfunction "NC_16") (pintype "passive"))
      (node (ref "LCD2") (pin "18") (pinfunction "VT_18") (pintype "passive"))
      (node (ref "LCD2") (pin "20") (pinfunction "BLK_20") (pintype "passive"))
      (node (ref "R13") (pin "2") (pinfunction "2_2") (pintype "passive"))
      (node (ref "R2") (pin "1") (pinfunction "1_1") (pintype "passive"))
      (node (ref "R3") (pin "1") (pinfunction "1_1") (pintype "passive"))
      (node (ref "R31") (pin "1") (pinfunction "1_1") (pintype "passive"))
      (node (ref "R39") (pin "2") (pinfunction "2_2") (pintype "passive"))
      (node (ref "R4") (pin "1") (pinfunction "1_1") (pintype "passive"))
      (node (ref "Rb1") (pin "1") (pinfunction "1_1") (pintype "passive"))
      (node (ref "Rb2") (pin "3") (pinfunction "3_3") (pintype "passive"))
      (node (ref "U1") (pin "16") (pinfunction "GND_16") (pintype "passive"))
      (node (ref "U10") (pin "8") (pinfunction "GND_8") (pintype "passive"))
      (node (ref "U11") (pin "4") (pinfunction "GND_4") (pintype "passive"))
      (node (ref "U14") (pin "2") (pinfunction "-IN_2") (pintype "passive"))
      (node (ref "U14") (pin "4") (pinfunction "GND_4") (pintype "passive"))
      (node (ref "U15") (pin "1") (pinfunction "GND_1") (pintype "passive"))
      (node (ref "U16") (pin "12") (pinfunction "EXT_12") (pintype "passive"))
      (node (ref "U16") (pin "13") (pinfunction "AGND_13") (pintype "passive"))
      (node (ref "U16") (pin "5") (pinfunction "A0_5") (pintype "passive"))
      (node (ref "U16") (pin "6") (pinfunction "A1_6") (pintype "passive"))
      (node (ref "U16") (pin "7") (pinfunction "A2_7") (pintype "passive"))
      (node (ref "U16") (pin "8") (pinfunction "VSS_8") (pintype "passive"))
      (node (ref "U18") (pin "7") (pinfunction "G_7") (pintype "passive"))
      (node (ref "U19") (pin "4") (pinfunction "GND_4") (pintype "passive"))
      (node (ref "U20") (pin "2") (pinfunction "GND_2") (pintype "passive"))
      (node (ref "U21") (pin "2") (pinfunction "GND_2") (pintype "passive"))
      (node (ref "U24") (pin "4") (pinfunction "G2A_4") (pintype "passive"))
      (node (ref "U24") (pin "5") (pinfunction "G2B_5") (pintype "passive"))
      (node (ref "U24") (pin "8") (pinfunction "GND_8") (pintype "passive"))
      (node (ref "U25") (pin "7") (pinfunction "GND_7") (pintype "passive"))
      (node (ref "U3") (pin "1") (pinfunction "GND_1") (pintype "passive"))
      (node (ref "U33") (pin "2") (pinfunction "GND_2") (pintype "passive"))
      (node (ref "U4") (pin "1") (pinfunction "A0_1") (pintype "passive"))
      (node (ref "U4") (pin "2") (pinfunction "A1_2") (pintype "passive"))
      (node (ref "U4") (pin "3") (pinfunction "A3_3") (pintype "passive"))
      (node (ref "U4") (pin "4") (pinfunction "GND_4") (pintype "passive"))
      (node (ref "U4") (pin "7") (pinfunction "WP_7") (pintype "passive"))
      (node (ref "U5") (pin "1") (pinfunction "GND_1") (pintype "passive"))
      (node (ref "U6") (pin "1") (pinfunction "OE_1") (pintype "passive"))
      (node (ref "U6") (pin "10") (pinfunction "GND_10") (pintype "passive"))
      (node (ref "U7") (pin "1") (pinfunction "OE_1") (pintype "passive"))
      (node (ref "U7") (pin "10") (pinfunction "GND_10") (pintype "passive"))
      (node (ref "U8") (pin "1") (pinfunction "OE_1") (pintype "passive"))
      (node (ref "U8") (pin "10") (pinfunction "GND_10") (pintype "passive"))
      (node (ref "U9") (pin "1") (pinfunction "OE_1") (pintype "passive"))
      (node (ref "U9") (pin "10") (pinfunction "GND_10") (pintype "passive"))
      (node (ref "USB1") (pin "-") (pinfunction "GND_-") (pintype "passive"))
      (node (ref "USB1") (pin "VSS1") (pintype "passive"))
      (node (ref "USB1") (pin "VSS2") (pintype "passive"))
      (node (ref "k1") (pin "1") (pinfunction "1_1") (pintype "passive"))
    )
    (net (code "109") (name "Net-(C3-Pad1)") (class "Default")
      (node (ref "C3") (pin "1") (pinfunction "1_1") (pintype "passive"))
      (node (ref "R2") (pin "2") (pinfunction "2_2") (pintype "passive"))
    )
    (net (code "110") (name "Net-(C7-Pad2)") (class "Default")
      (node (ref "C7") (pin "2") (pinfunction "2_2") (pintype "passive"))
      (node (ref "JS2") (pin "1") (pinfunction "1_1") (pintype "passive"))
    )
    (net (code "111") (name "Net-(C8-Pad2)") (class "Default")
      (node (ref "C8") (pin "2") (pinfunction "2_2") (pintype "passive"))
      (node (ref "JS2") (pin "2") (pinfunction "2_2") (pintype "passive"))
    )
    (net (code "112") (name "Net-(C17-Pad1)") (class "Default")
      (node (ref "C17") (pin "1") (pinfunction "1_1") (pintype "passive"))
      (node (ref "R23") (pin "2") (pinfunction "2_2") (pintype "passive"))
    )
    (net (code "113") (name "Net-(C18-+)") (class "Default")
      (node (ref "C18") (pin "1") (pinfunction "+_1") (pintype "passive"))
      (node (ref "R23") (pin "1") (pinfunction "1_1") (pintype "passive"))
      (node (ref "U14") (pin "5") (pinfunction "OUT_5") (pintype "passive"))
    )
    (net (code "114") (name "Net-(C19--)") (class "Default")
      (node (ref "C19") (pin "2") (pinfunction "-_2") (pintype "passive"))
      (node (ref "D2") (pin "2") (pinfunction "2_2") (pintype "passive"))
      (node (ref "D3") (pin "1") (pinfunction "1_1") (pintype "passive"))
    )
    (net (code "115") (name "Net-(J5-Pad2)") (class "Default")
      (node (ref "J5") (pin "2") (pinfunction "2_2") (pintype "passive"))
      (node (ref "S4") (pin "2") (pinfunction "2_2") (pintype "passive"))
      (node (ref "S5") (pin "2") (pinfunction "2_2") (pintype "passive"))
      (node (ref "S6") (pin "2") (pinfunction "2_2") (pintype "passive"))
      (node (ref "S7") (pin "2") (pinfunction "2_2") (pintype "passive"))
    )
    (net (code "116") (name "Net-(L1-Pad1)") (class "Default")
      (node (ref "L1") (pin "1") (pinfunction "1_1") (pintype "passive"))
      (node (ref "R32") (pin "2") (pinfunction "2_2") (pintype "passive"))
    )
    (net (code "117") (name "Net-(L2-Pad1)") (class "Default")
      (node (ref "L2") (pin "1") (pinfunction "1_1") (pintype "passive"))
      (node (ref "R33") (pin "2") (pinfunction "2_2") (pintype "passive"))
    )
    (net (code "118") (name "Net-(L3-Pad1)") (class "Default")
      (node (ref "L3") (pin "1") (pinfunction "1_1") (pintype "passive"))
      (node (ref "R40") (pin "2") (pinfunction "2_2") (pintype "passive"))
    )
    (net (code "119") (name "Net-(L4-Pad1)") (class "Default")
      (node (ref "L4") (pin "1") (pinfunction "1_1") (pintype "passive"))
      (node (ref "R41") (pin "2") (pinfunction "2_2") (pintype "passive"))
    )
    (net (code "120") (name "Net-(L5-Pad1)") (class "Default")
      (node (ref "L5") (pin "1") (pinfunction "1_1") (pintype "passive"))
      (node (ref "R42") (pin "2") (pinfunction "2_2") (pintype "passive"))
    )
    (net (code "121") (name "Net-(L6-Pad1)") (class "Default")
      (node (ref "L6") (pin "1") (pinfunction "1_1") (pintype "passive"))
      (node (ref "R43") (pin "2") (pinfunction "2_2") (pintype "passive"))
    )
    (net (code "122") (name "Net-(L7-Pad1)") (class "Default")
      (node (ref "L7") (pin "1") (pinfunction "1_1") (pintype "passive"))
      (node (ref "R44") (pin "2") (pinfunction "2_2") (pintype "passive"))
    )
    (net (code "123") (name "Net-(L8-Pad1)") (class "Default")
      (node (ref "L8") (pin "1") (pinfunction "1_1") (pintype "passive"))
      (node (ref "R45") (pin "2") (pinfunction "2_2") (pintype "passive"))
    )
    (net (code "124") (name "Net-(L9-Pad2)") (class "Default")
      (node (ref "L9") (pin "2") (pinfunction "2_2") (pintype "passive"))
      (node (ref "R4") (pin "2") (pinfunction "2_2") (pintype "passive"))
    )
    (net (code "125") (name "Net-(L10-Pad2)") (class "Default")
      (node (ref "L10") (pin "2") (pinfunction "2_2") (pintype "passive"))
      (node (ref "R24") (pin "2") (pinfunction "2_2") (pintype "passive"))
    )
    (net (code "126") (name "Net-(L11-Pad2)") (class "Default")
      (node (ref "L11") (pin "2") (pinfunction "2_2") (pintype "passive"))
      (node (ref "R27") (pin "2") (pinfunction "2_2") (pintype "passive"))
    )
    (net (code "127") (name "Net-(L12-Pad2)") (class "Default")
      (node (ref "L12") (pin "2") (pinfunction "2_2") (pintype "passive"))
      (node (ref "R1") (pin "2") (pinfunction "2_2") (pintype "passive"))
    )
    (net (code "128") (name "Net-(LD1-Pad2)") (class "Default")
      (node (ref "LD1") (pin "2") (pinfunction "2_2") (pintype "passive"))
      (node (ref "R12") (pin "2") (pinfunction "2_2") (pintype "passive"))
    )
    (net (code "129") (name "Net-(R8-Pad1)") (class "Default")
      (node (ref "R8") (pin "1") (pinfunction "1_1") (pintype "passive"))
      (node (ref "RB3") (pin "1") (pinfunction "1_1") (pintype "passive"))
    )
    (net (code "130") (name "Net-(U3-RXD)") (class "Default")
      (node (ref "R28") (pin "1") (pinfunction "1_1") (pintype "passive"))
      (node (ref "U3") (pin "3") (pinfunction "RXD_3") (pintype "passive"))
    )
    (net (code "131") (name "Net-(U3-TXD)") (class "Default")
      (node (ref "D4") (pin "2") (pinfunction "2_2") (pintype "passive"))
      (node (ref "U3") (pin "2") (pinfunction "TXD_2") (pintype "passive"))
    )
    (net (code "132") (name "Net-(U3-V3)") (class "Default")
      (node (ref "C5") (pin "2") (pinfunction "2_2") (pintype "passive"))
      (node (ref "U3") (pin "4") (pinfunction "V3_4") (pintype "passive"))
    )
    (net (code "133") (name "Net-(U6-Q1)") (class "Default")
      (node (ref "L1") (pin "2") (pinfunction "2_2") (pintype "passive"))
      (node (ref "U6") (pin "19") (pinfunction "Q1_19") (pintype "passive"))
    )
    (net (code "134") (name "Net-(U6-Q2)") (class "Default")
      (node (ref "L2") (pin "2") (pinfunction "2_2") (pintype "passive"))
      (node (ref "U6") (pin "18") (pinfunction "Q2_18") (pintype "passive"))
    )
    (net (code "135") (name "Net-(U6-Q3)") (class "Default")
      (node (ref "L3") (pin "2") (pinfunction "2_2") (pintype "passive"))
      (node (ref "U6") (pin "17") (pinfunction "Q3_17") (pintype "passive"))
    )
    (net (code "136") (name "Net-(U6-Q4)") (class "Default")
      (node (ref "L4") (pin "2") (pinfunction "2_2") (pintype "passive"))
      (node (ref "U6") (pin "16") (pinfunction "Q4_16") (pintype "passive"))
    )
    (net (code "137") (name "Net-(U6-Q5)") (class "Default")
      (node (ref "L5") (pin "2") (pinfunction "2_2") (pintype "passive"))
      (node (ref "U6") (pin "15") (pinfunction "Q5_15") (pintype "passive"))
    )
    (net (code "138") (name "Net-(U6-Q6)") (class "Default")
      (node (ref "L6") (pin "2") (pinfunction "2_2") (pintype "passive"))
      (node (ref "U6") (pin "14") (pinfunction "Q6_14") (pintype "passive"))
    )
    (net (code "139") (name "Net-(U6-Q7)") (class "Default")
      (node (ref "L7") (pin "2") (pinfunction "2_2") (pintype "passive"))
      (node (ref "U6") (pin "13") (pinfunction "Q7_13") (pintype "passive"))
    )
    (net (code "140") (name "Net-(U6-Q8)") (class "Default")
      (node (ref "L8") (pin "2") (pinfunction "2_2") (pintype "passive"))
      (node (ref "U6") (pin "12") (pinfunction "Q8_12") (pintype "passive"))
    )
    (net (code "141") (name "Net-(U10-IN1)") (class "Default")
      (node (ref "U10") (pin "1") (pinfunction "IN1_1") (pintype "passive"))
      (node (ref "U9") (pin "19") (pinfunction "Q1_19") (pintype "passive"))
    )
    (net (code "142") (name "Net-(U10-IN2)") (class "Default")
      (node (ref "U10") (pin "2") (pinfunction "IN2_2") (pintype "passive"))
      (node (ref "U9") (pin "18") (pinfunction "Q2_18") (pintype "passive"))
    )
    (net (code "143") (name "Net-(U10-IN3)") (class "Default")
      (node (ref "U10") (pin "3") (pinfunction "IN3_3") (pintype "passive"))
      (node (ref "U9") (pin "17") (pinfunction "Q3_17") (pintype "passive"))
    )
    (net (code "144") (name "Net-(U10-IN4)") (class "Default")
      (node (ref "U10") (pin "4") (pinfunction "IN4_4") (pintype "passive"))
      (node (ref "U9") (pin "16") (pinfunction "Q4_16") (pintype "passive"))
    )
    (net (code "145") (name "Net-(U10-IN5)") (class "Default")
      (node (ref "U10") (pin "5") (pinfunction "IN5_5") (pintype "passive"))
      (node (ref "U9") (pin "15") (pinfunction "Q5_15") (pintype "passive"))
    )
    (net (code "146") (name "Net-(U10-IN6)") (class "Default")
      (node (ref "U10") (pin "6") (pinfunction "IN6_6") (pintype "passive"))
      (node (ref "U9") (pin "14") (pinfunction "Q6_14") (pintype "passive"))
    )
    (net (code "147") (name "Net-(U10-IN7)") (class "Default")
      (node (ref "U10") (pin "7") (pinfunction "IN7_7") (pintype "passive"))
      (node (ref "U9") (pin "13") (pinfunction "Q7_13") (pintype "passive"))
    )
    (net (code "148") (name "Net-(U11-C1)") (class "Default")
      (node (ref "C3") (pin "2") (pinfunction "2_2") (pintype "passive"))
      (node (ref "U11") (pin "2") (pinfunction "C1_2") (pintype "passive"))
    )
    (net (code "149") (name "Net-(U11-C2)") (class "Default")
      (node (ref "C4") (pin "2") (pinfunction "2_2") (pintype "passive"))
      (node (ref "U11") (pin "3") (pinfunction "C2_3") (pintype "passive"))
    )
    (net (code "150") (name "Net-(U11-C3)") (class "Default")
      (node (ref "C6") (pin "2") (pinfunction "2_2") (pintype "passive"))
      (node (ref "U11") (pin "6") (pinfunction "C3_6") (pintype "passive"))
    )
    (net (code "151") (name "Net-(U11-FA)") (class "Default")
      (node (ref "R5") (pin "2") (pinfunction "2_2") (pintype "passive"))
      (node (ref "U11") (pin "5") (pinfunction "FA_5") (pintype "passive"))
    )
    (net (code "152") (name "Net-(U11-IN)") (class "Default")
      (node (ref "C1") (pin "2") (pinfunction "2_2") (pintype "passive"))
      (node (ref "JS1") (pin "1") (pinfunction "1_1") (pintype "passive"))
      (node (ref "U11") (pin "1") (pinfunction "IN_1") (pintype "passive"))
    )
    (net (code "153") (name "Net-(U14-+IN)") (class "Default")
      (node (ref "R13") (pin "1") (pinfunction "1_1") (pintype "passive"))
      (node (ref "R14") (pin "1") (pinfunction "1_1") (pintype "passive"))
      (node (ref "U14") (pin "3") (pinfunction "+IN_3") (pintype "passive"))
    )
    (net (code "154") (name "Net-(U15-CVOLT)") (class "Default")
      (node (ref "C16") (pin "1") (pinfunction "1_1") (pintype "passive"))
      (node (ref "U15") (pin "5") (pinfunction "CVOLT_5") (pintype "passive"))
    )
    (net (code "155") (name "Net-(U15-THR)") (class "Default")
      (node (ref "C14") (pin "2") (pinfunction "2_2") (pintype "passive"))
      (node (ref "R8") (pin "2") (pinfunction "2_2") (pintype "passive"))
      (node (ref "U15") (pin "2") (pinfunction "TRIG_2") (pintype "passive"))
      (node (ref "U15") (pin "6") (pinfunction "THR_6") (pintype "passive"))
    )
    (net (code "156") (name "Net-(U18-1A)") (class "Default")
      (node (ref "U18") (pin "1") (pinfunction "1A_1") (pintype "passive"))
      (node (ref "U18") (pin "6") (pinfunction "3B_6") (pintype "passive"))
      (node (ref "U18") (pin "9") (pinfunction "6A_9") (pintype "passive"))
    )
    (net (code "157") (name "Net-(U18-1B)") (class "Default")
      (node (ref "C8") (pin "1") (pinfunction "1_1") (pintype "passive"))
      (node (ref "U18") (pin "2") (pinfunction "1B_2") (pintype "passive"))
      (node (ref "U18") (pin "8") (pinfunction "6B_8") (pintype "passive"))
    )
    (net (code "158") (name "Net-(U18-2B)") (class "Default")
      (node (ref "U18") (pin "11") (pinfunction "5A_11") (pintype "passive"))
      (node (ref "U18") (pin "13") (pinfunction "4A_13") (pintype "passive"))
      (node (ref "U18") (pin "4") (pinfunction "2B_4") (pintype "passive"))
      (node (ref "U18") (pin "5") (pinfunction "3A_5") (pintype "passive"))
    )
    (net (code "159") (name "Net-(U18-4B)") (class "Default")
      (node (ref "C7") (pin "1") (pinfunction "1_1") (pintype "passive"))
      (node (ref "U18") (pin "10") (pinfunction "5B_10") (pintype "passive"))
      (node (ref "U18") (pin "12") (pinfunction "4B_12") (pintype "passive"))
    )
    (net (code "160") (name "Net-(U19-X1)") (class "Default")
      (node (ref "U19") (pin "2") (pinfunction "X1_2") (pintype "passive"))
      (node (ref "Y3") (pin "2") (pinfunction "2_2") (pintype "passive"))
    )
    (net (code "161") (name "Net-(U19-X2)") (class "Default")
      (node (ref "U19") (pin "3") (pinfunction "X2_3") (pintype "passive"))
      (node (ref "Y3") (pin "1") (pinfunction "1_1") (pintype "passive"))
    )
    (net (code "162") (name "Net-(U26-IN1-)") (class "Default")
      (node (ref "R34") (pin "2") (pinfunction "2_2") (pintype "passive"))
      (node (ref "RB4") (pin "1") (pinfunction "1_1") (pintype "passive"))
      (node (ref "U26") (pin "2") (pinfunction "IN1-_2") (pintype "passive"))
    )
    (net (code "163") (name "Net-(U26-IN2+)") (class "Default")
      (node (ref "R37") (pin "2") (pinfunction "2_2") (pintype "passive"))
      (node (ref "R39") (pin "1") (pinfunction "1_1") (pintype "passive"))
      (node (ref "U26") (pin "5") (pinfunction "IN2+_5") (pintype "passive"))
    )
    (net (code "164") (name "Net-(U26-IN2-)") (class "Default")
      (node (ref "R36") (pin "2") (pinfunction "2_2") (pintype "passive"))
      (node (ref "R38") (pin "1") (pinfunction "1_1") (pintype "passive"))
      (node (ref "U26") (pin "6") (pinfunction "IN2-_6") (pintype "passive"))
    )
    (net (code "165") (name "Net-(U26-IN3-)") (class "Default")
      (node (ref "R35") (pin "1") (pinfunction "1_1") (pintype "passive"))
      (node (ref "RB4") (pin "2") (pinfunction "2_2") (pintype "passive"))
      (node (ref "RB4") (pin "3") (pinfunction "3_3") (pintype "passive"))
      (node (ref "U26") (pin "9") (pinfunction "IN3-_9") (pintype "passive"))
    )
    (net (code "166") (name "Net-(U26-OU1)") (class "Default")
      (node (ref "R34") (pin "1") (pinfunction "1_1") (pintype "passive"))
      (node (ref "R36") (pin "1") (pinfunction "1_1") (pintype "passive"))
      (node (ref "U26") (pin "1") (pinfunction "OU1_1") (pintype "passive"))
    )
    (net (code "167") (name "Net-(U26-OU3)") (class "Default")
      (node (ref "R35") (pin "2") (pinfunction "2_2") (pintype "passive"))
      (node (ref "R37") (pin "1") (pinfunction "1_1") (pintype "passive"))
      (node (ref "U26") (pin "8") (pinfunction "OU3_8") (pintype "passive"))
    )
    (net (code "168") (name "VCC") (class "Default")
      (node (ref "BEEP") (pin "1") (pinfunction "+_1") (pintype "passive"))
      (node (ref "C11") (pin "2") (pinfunction "2_2") (pintype "passive"))
      (node (ref "C12") (pin "2") (pinfunction "2_2") (pintype "passive"))
      (node (ref "C13") (pin "2") (pinfunction "2_2") (pintype "passive"))
      (node (ref "C15") (pin "2") (pinfunction "2_2") (pintype "passive"))
      (node (ref "C2") (pin "2") (pinfunction "2_2") (pintype "passive"))
      (node (ref "C21") (pin "1") (pinfunction "+_1") (pintype "passive"))
      (node (ref "C22") (pin "1") (pinfunction "1_1") (pintype "passive"))
      (node (ref "CR1") (pin "2") (pinfunction "2_2") (pintype "passive"))
      (node (ref "D1") (pin "2") (pinfunction "2_2") (pintype "passive"))
      (node (ref "J10") (pin "18") (pinfunction "18_18") (pintype "passive"))
      (node (ref "J10") (pin "19") (pinfunction "19_19") (pintype "passive"))
      (node (ref "J11") (pin "1") (pinfunction "1_1") (pintype "passive"))
      (node (ref "J11") (pin "10") (pinfunction "10_10") (pintype "passive"))
      (node (ref "J12") (pin "1") (pinfunction "VCC_1") (pintype "passive"))
      (node (ref "J12") (pin "2") (pinfunction "VCC_2") (pintype "passive"))
      (node (ref "J12") (pin "3") (pinfunction "VCC_3") (pintype "passive"))
      (node (ref "J12") (pin "4") (pinfunction "VCC_4") (pintype "passive"))
      (node (ref "J12") (pin "5") (pinfunction "VCC_5") (pintype "passive"))
      (node (ref "J3") (pin "5") (pinfunction "5_5") (pintype "passive"))
      (node (ref "J3") (pin "7") (pinfunction "7_7") (pintype "passive"))
      (node (ref "J3") (pin "8") (pinfunction "8_8") (pintype "passive"))
      (node (ref "J7") (pin "1") (pinfunction "1_1") (pintype "passive"))
      (node (ref "L10") (pin "1") (pinfunction "1_1") (pintype "passive"))
      (node (ref "L11") (pin "1") (pinfunction "1_1") (pintype "passive"))
      (node (ref "L12") (pin "1") (pinfunction "1_1") (pintype "passive"))
      (node (ref "LCD1") (pin "15") (pinfunction "BLA_15") (pintype "passive"))
      (node (ref "LCD1") (pin "2") (pinfunction "VDD_2") (pintype "passive"))
      (node (ref "LCD2") (pin "17") (pinfunction "RES_17") (pintype "passive"))
      (node (ref "LCD2") (pin "19") (pinfunction "BLA_19") (pintype "passive"))
      (node (ref "LCD2") (pin "2") (pinfunction "VDD_2") (pintype "passive"))
      (node (ref "LD1") (pin "1") (pinfunction "1_1") (pintype "passive"))
      (node (ref "R10") (pin "1") (pinfunction "1_1") (pintype "passive"))
      (node (ref "R11") (pin "1") (pinfunction "1_1") (pintype "passive"))
      (node (ref "R32") (pin "1") (pinfunction "1_1") (pintype "passive"))
      (node (ref "R33") (pin "1") (pinfunction "1_1") (pintype "passive"))
      (node (ref "R40") (pin "1") (pinfunction "1_1") (pintype "passive"))
      (node (ref "R41") (pin "1") (pinfunction "1_1") (pintype "passive"))
      (node (ref "R42") (pin "1") (pinfunction "1_1") (pintype "passive"))
      (node (ref "R43") (pin "1") (pinfunction "1_1") (pintype "passive"))
      (node (ref "R44") (pin "1") (pinfunction "1_1") (pintype "passive"))
      (node (ref "R45") (pin "1") (pinfunction "1_1") (pintype "passive"))
      (node (ref "R5") (pin "1") (pinfunction "1_1") (pintype "passive"))
      (node (ref "R6") (pin "1") (pinfunction "1_1") (pintype "passive"))
      (node (ref "R7") (pin "2") (pinfunction "2_2") (pintype "passive"))
      (node (ref "R9") (pin "2") (pinfunction "2_2") (pintype "passive"))
      (node (ref "RD1") (pin "1") (pinfunction "1_1") (pintype "passive"))
      (node (ref "Rb1") (pin "3") (pinfunction "3_3") (pintype "passive"))
      (node (ref "Rb2") (pin "1") (pinfunction "1_1") (pintype "passive"))
      (node (ref "S1") (pin "1") (pinfunction "1_1") (pintype "passive"))
      (node (ref "S3") (pin "2") (pinfunction "2_2") (pintype "passive"))
      (node (ref "U1") (pin "14") (pinfunction "VCC_14") (pintype "passive"))
      (node (ref "U1") (pin "15") (pinfunction "P55_15") (pintype "passive"))
      (node (ref "U10") (pin "9") (pinfunction "COM_9") (pintype "passive"))
      (node (ref "U11") (pin "8") (pinfunction "VCC_8") (pintype "passive"))
      (node (ref "U14") (pin "6") (pinfunction "VS_6") (pintype "passive"))
      (node (ref "U15") (pin "4") (pinfunction "RST_4") (pintype "passive"))
      (node (ref "U15") (pin "8") (pinfunction "VCC_8") (pintype "passive"))
      (node (ref "U16") (pin "14") (pinfunction "VREF_14") (pintype "passive"))
      (node (ref "U16") (pin "16") (pinfunction "VDD_16") (pintype "passive"))
      (node (ref "U18") (pin "14") (pinfunction "V_14") (pintype "passive"))
      (node (ref "U19") (pin "1") (pinfunction "VCC2_1") (pintype "passive"))
      (node (ref "U20") (pin "3") (pinfunction "VDD_3") (pintype "passive"))
      (node (ref "U21") (pin "1") (pinfunction "VDD_1") (pintype "passive"))
      (node (ref "U24") (pin "16") (pinfunction "VCC_16") (pintype "passive"))
      (node (ref "U24") (pin "6") (pinfunction "G1_6") (pintype "passive"))
      (node (ref "U25") (pin "14") (pinfunction "VCC_14") (pintype "passive"))
      (node (ref "U26") (pin "4") (pinfunction "VCC_4") (pintype "passive"))
      (node (ref "U33") (pin "1") (pinfunction "VCC_1") (pintype "passive"))
      (node (ref "U4") (pin "8") (pinfunction "VCC_8") (pintype "passive"))
      (node (ref "U5") (pin "3") (pinfunction "VDD_3") (pintype "passive"))
      (node (ref "U6") (pin "20") (pinfunction "VCC_20") (pintype "passive"))
      (node (ref "U7") (pin "20") (pinfunction "VCC_20") (pintype "passive"))
      (node (ref "U8") (pin "20") (pinfunction "VCC_20") (pintype "passive"))
      (node (ref "U9") (pin "20") (pinfunction "VCC_20") (pintype "passive"))
      (node (ref "k1") (pin "5") (pinfunction "5_5") (pintype "passive"))
    )
    (net (code "169") (name "VCCA") (class "Default")
      (node (ref "C10") (pin "1") (pinfunction "+_1") (pintype "passive"))
      (node (ref "C27") (pin "1") (pinfunction "+_1") (pintype "passive"))
      (node (ref "C9") (pin "2") (pinfunction "2_2") (pintype "passive"))
      (node (ref "J1") (pin "VCCA") (pinfunction "VCCA_VCCA") (pintype "passive"))
      (node (ref "L9") (pin "1") (pinfunction "1_1") (pintype "passive"))
      (node (ref "S3") (pin "3") (pinfunction "3_3") (pintype "passive"))
      (node (ref "U3") (pin "16") (pinfunction "VCC_16") (pintype "passive"))
      (node (ref "USB1") (pin "+") (pinfunction "VCC_+") (pintype "passive"))
    )
    (net (code "170") (name "unconnected-(S3-Pad1)") (class "Default")
      (node (ref "S3") (pin "1") (pinfunction "1_1") (pintype "passive"))
    )
    (net (code "171") (name "unconnected-(S3-Pad4)") (class "Default")
      (node (ref "S3") (pin "4") (pinfunction "4_4") (pintype "passive"))
    )
    (net (code "172") (name "unconnected-(S3-Pad5)") (class "Default")
      (node (ref "S3") (pin "5") (pinfunction "5_5") (pintype "passive"))
    )
    (net (code "173") (name "unconnected-(S3-Pad6)") (class "Default")
      (node (ref "S3") (pin "6") (pinfunction "6_6") (pintype "passive"))
    )
    (net (code "174") (name "unconnected-(U3-CTS#-Pad9)") (class "Default")
      (node (ref "U3") (pin "9") (pinfunction "CTS#_9") (pintype "passive"))
    )
    (net (code "175") (name "unconnected-(U3-DCD#-Pad12)") (class "Default")
      (node (ref "U3") (pin "12") (pinfunction "DCD#_12") (pintype "passive"))
    )
    (net (code "176") (name "unconnected-(U3-DSR#-Pad10)") (class "Default")
      (node (ref "U3") (pin "10") (pinfunction "DSR#_10") (pintype "passive"))
    )
    (net (code "177") (name "unconnected-(U3-DTR#-Pad13)") (class "Default")
      (node (ref "U3") (pin "13") (pinfunction "DTR#_13") (pintype "passive"))
    )
    (net (code "178") (name "unconnected-(U3-NC-Pad7)") (class "Default")
      (node (ref "U3") (pin "7") (pinfunction "NC_7") (pintype "passive"))
    )
    (net (code "179") (name "unconnected-(U3-OUT#-Pad8)") (class "Default")
      (node (ref "U3") (pin "8") (pinfunction "OUT#_8") (pintype "passive"))
    )
    (net (code "180") (name "unconnected-(U3-RI#-Pad11)") (class "Default")
      (node (ref "U3") (pin "11") (pinfunction "RI#_11") (pintype "passive"))
    )
    (net (code "181") (name "unconnected-(U3-RS232-Pad15)") (class "Default")
      (node (ref "U3") (pin "15") (pinfunction "RS232_15") (pintype "passive"))
    )
    (net (code "182") (name "unconnected-(U3-RTS#-Pad14)") (class "Default")
      (node (ref "U3") (pin "14") (pinfunction "RTS#_14") (pintype "passive"))
    )
    (net (code "183") (name "unconnected-(U14-BYPASS-Pad7)") (class "Default")
      (node (ref "U14") (pin "7") (pinfunction "BYPASS_7") (pintype "passive"))
    )
    (net (code "184") (name "unconnected-(U14-GAIN-Pad1)") (class "Default")
      (node (ref "U14") (pin "1") (pinfunction "GAIN_1") (pintype "passive"))
    )
    (net (code "185") (name "unconnected-(U14-GAIN-Pad8)") (class "Default")
      (node (ref "U14") (pin "8") (pinfunction "GAIN_8") (pintype "passive"))
    )
    (net (code "186") (name "unconnected-(U15-DISC-Pad7)") (class "Default")
      (node (ref "U15") (pin "7") (pinfunction "DISC_7") (pintype "passive"))
    )
    (net (code "187") (name "unconnected-(U16-OSC-Pad11)") (class "Default")
      (node (ref "U16") (pin "11") (pinfunction "OSC_11") (pintype "passive"))
    )
    (net (code "188") (name "unconnected-(U26-IN4+-Pad12)") (class "Default")
      (node (ref "U26") (pin "12") (pinfunction "IN4+_12") (pintype "passive"))
    )
    (net (code "189") (name "unconnected-(U26-IN4--Pad13)") (class "Default")
      (node (ref "U26") (pin "13") (pinfunction "IN4-_13") (pintype "passive"))
    )
    (net (code "190") (name "unconnected-(U26-OU4-Pad14)") (class "Default")
      (node (ref "U26") (pin "14") (pinfunction "OU4_14") (pintype "passive"))
    )
  )
)
